# Evaluation_Board_v1_0.net
KiCad netlist of a schematic drawn in EAGLE
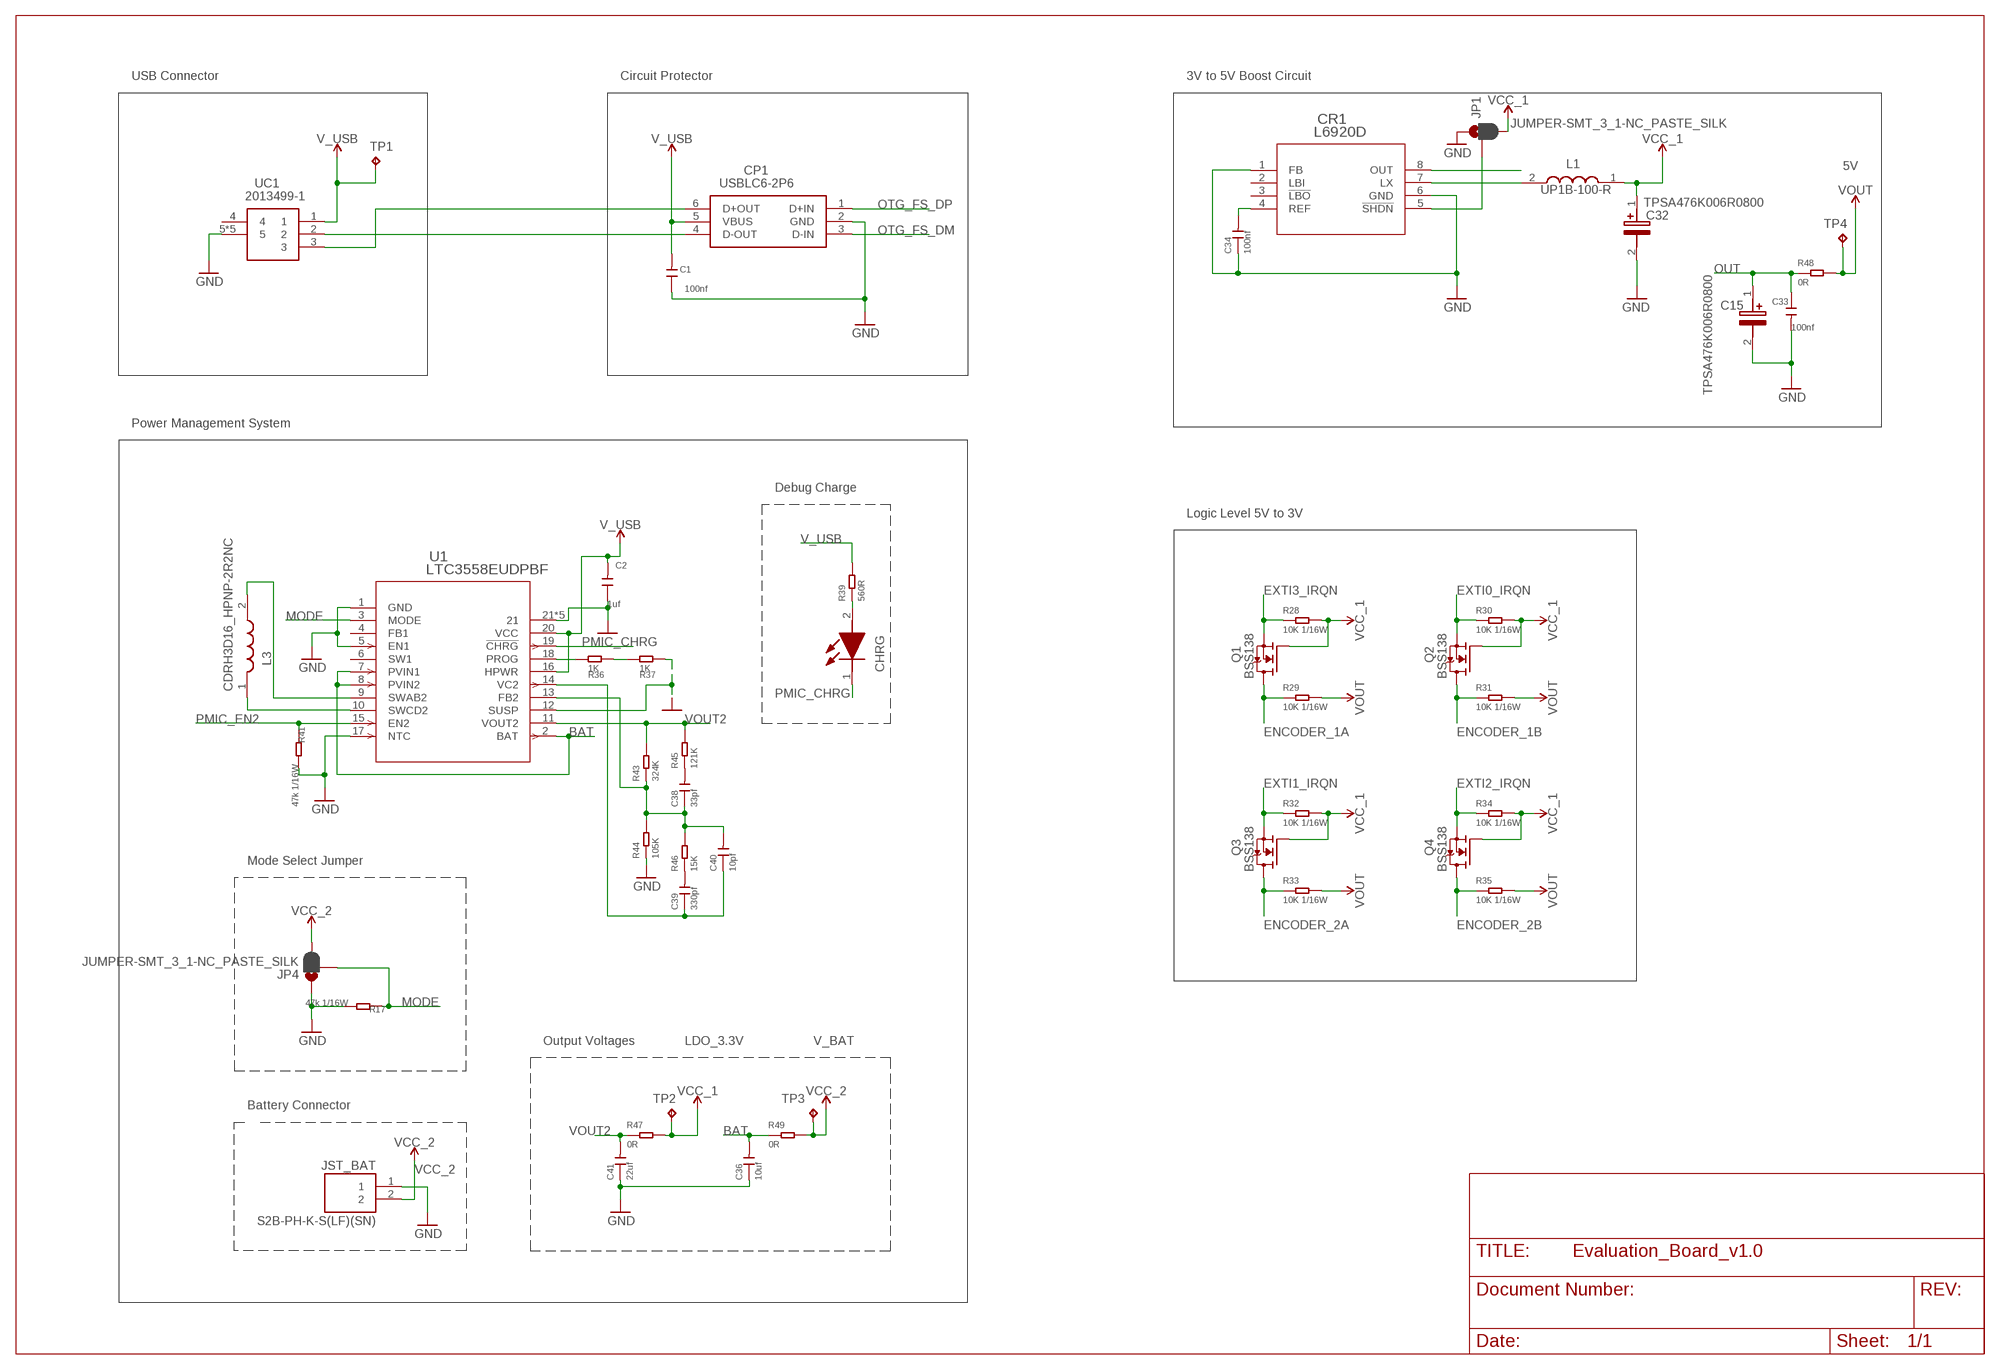
[diagram p0: schematic, sheet 1, part 1 of 3]
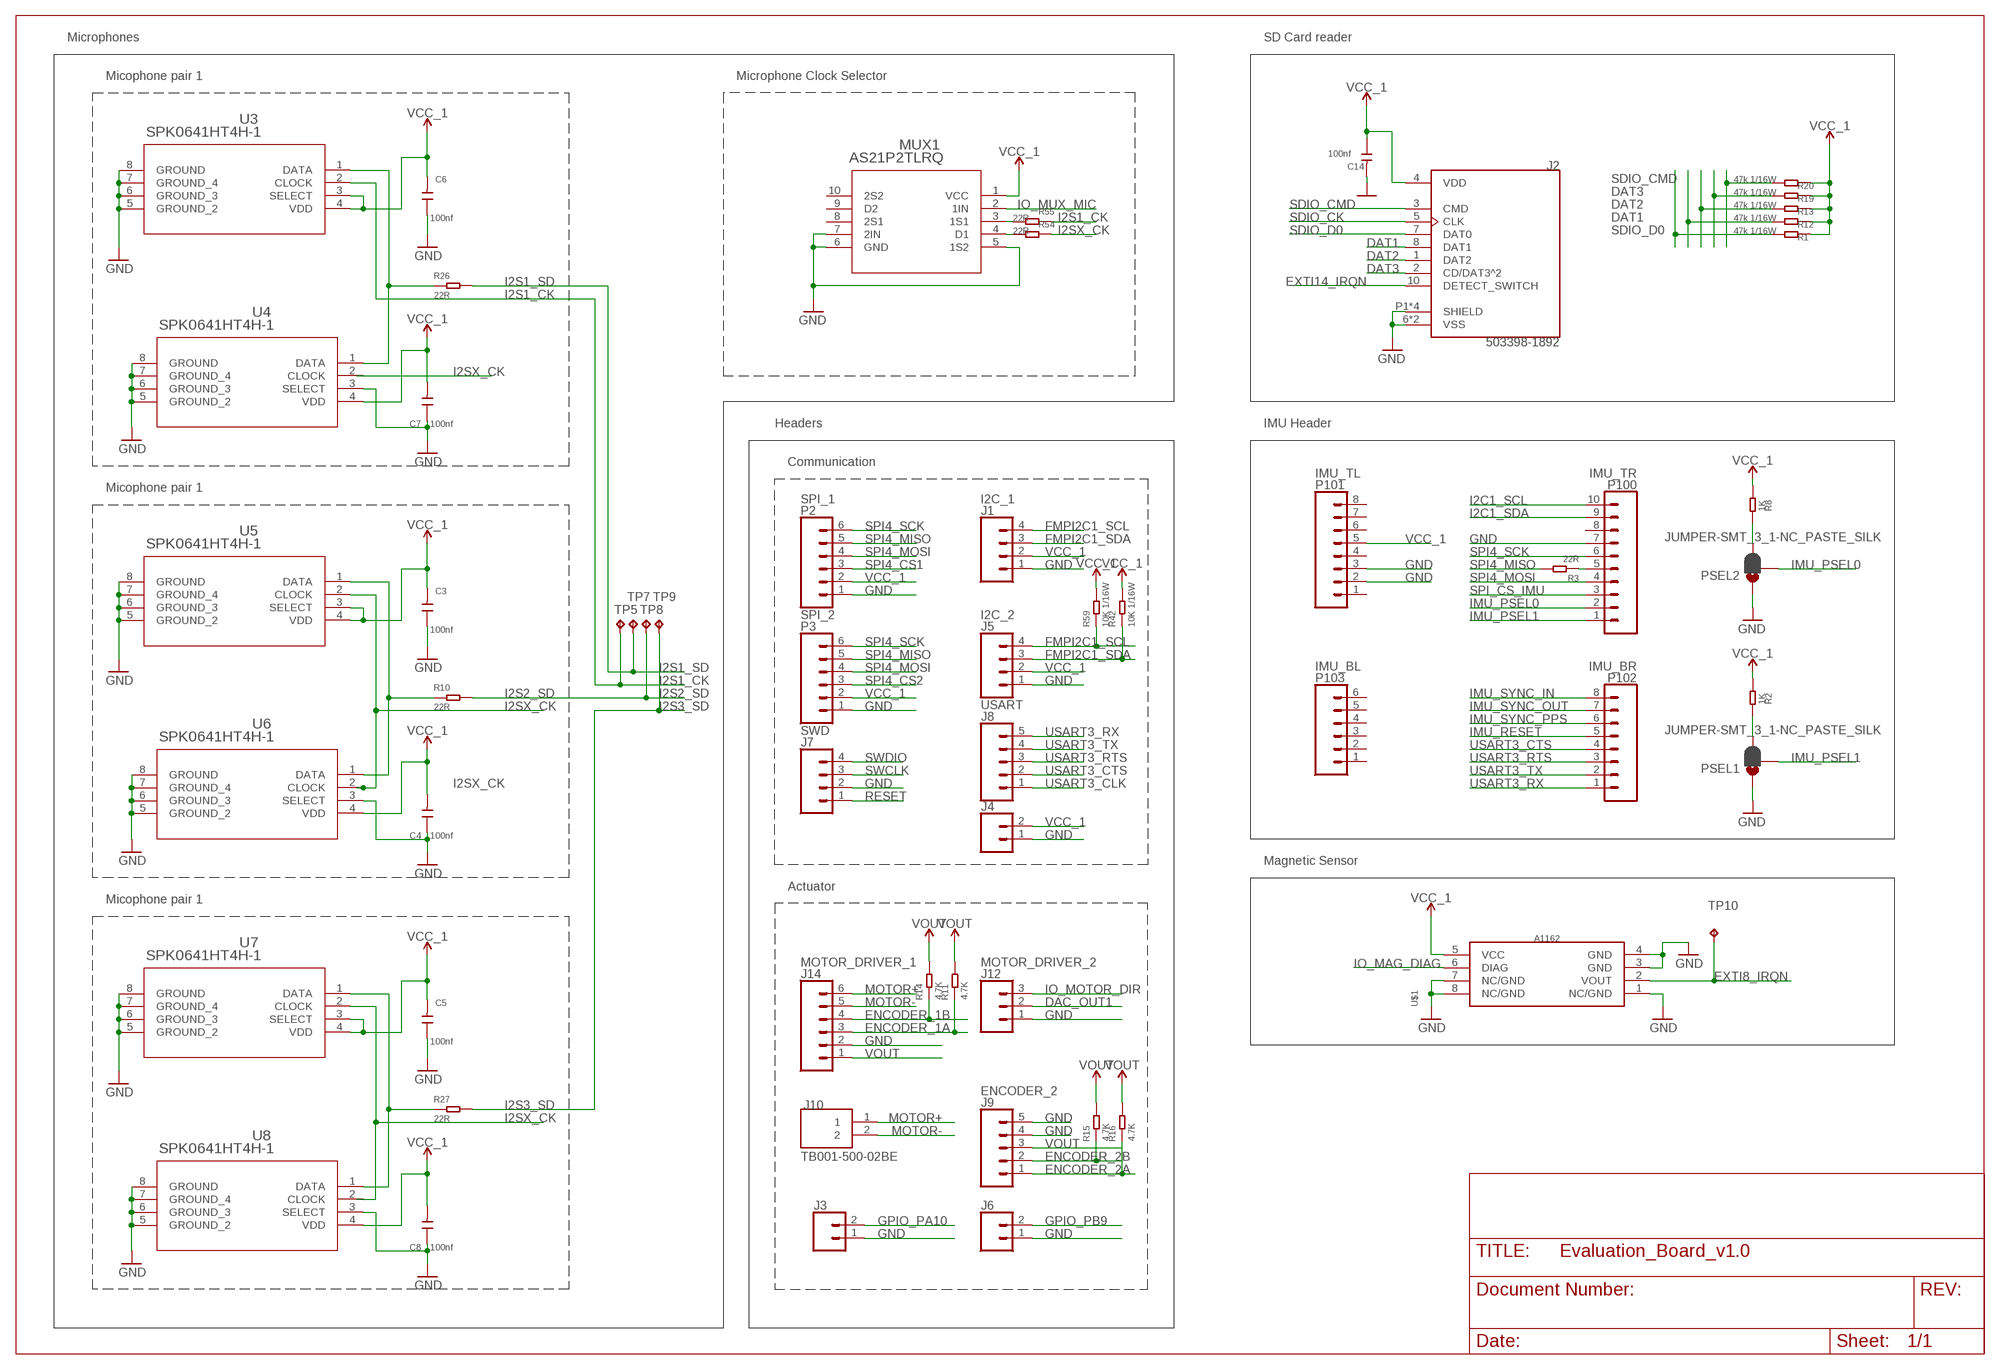
[diagram p1: schematic, sheet 1, part 2 of 3]
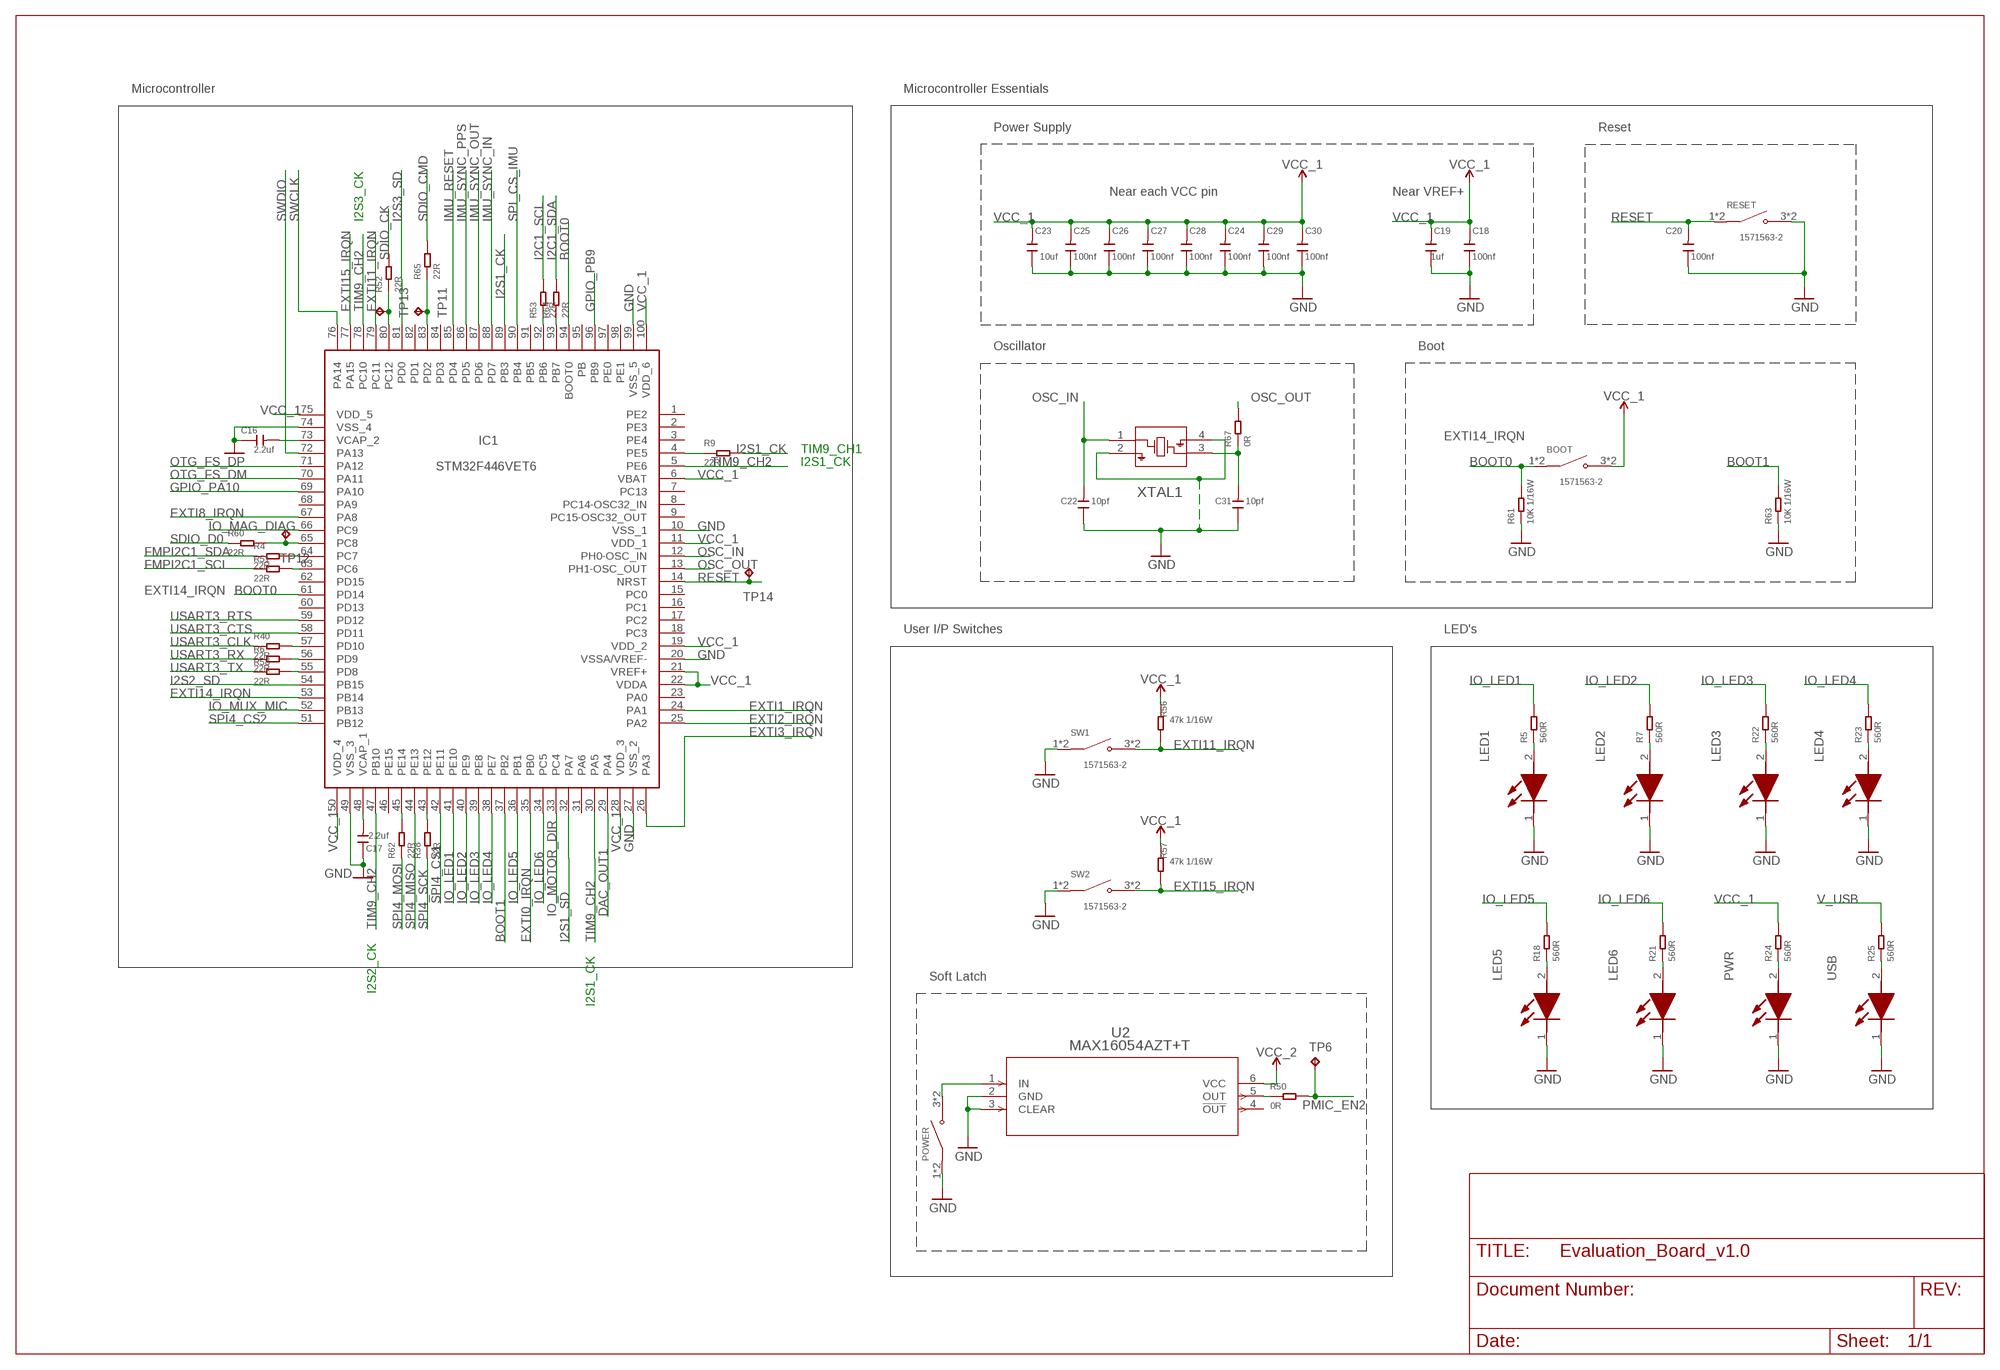
[diagram p2: schematic, sheet 1, part 3 of 3]

(export (version "E")
  (design (tool "Eeschema 10.0.6"))
  (components
    (comp (ref "BOOT")
      (value "1571563-2")
      (footprint "eagle-import:SW_1571563-2")
      (fields (field (name "DIGI-KEY_PART_NUMBER") "450-2057-1-ND") (field (name "MF") "TE Connectivity"))
      (libsource (lib "eagle-import") (part "1571563-2"))
    )
    (comp (ref "C1")
      (value "100nf")
      (footprint "eagle-import:C0402")
      (fields (field (name "MPN") "CC0402KRX7R8BB104"))
      (libsource (lib "eagle-import") (part "CERAMIC-100NF-25V-10%-X7R(0402)"))
    )
    (comp (ref "C2")
      (value "1uf")
      (footprint "eagle-import:C0402")
      (fields (field (name "MPN") "CC0402KRX5R6BB105"))
      (libsource (lib "eagle-import") (part "CERAMIC-1UF-10V-10%-X5R(0402)"))
    )
    (comp (ref "C3")
      (value "100nf")
      (footprint "eagle-import:C0402")
      (fields (field (name "MPN") "CC0402KRX7R8BB104"))
      (libsource (lib "eagle-import") (part "CERAMIC-100NF-25V-10%-X7R(0402)"))
    )
    (comp (ref "C4")
      (value "100nf")
      (footprint "eagle-import:C0402")
      (fields (field (name "MPN") "CC0402KRX7R8BB104"))
      (libsource (lib "eagle-import") (part "CERAMIC-100NF-25V-10%-X7R(0402)"))
    )
    (comp (ref "C5")
      (value "100nf")
      (footprint "eagle-import:C0402")
      (fields (field (name "MPN") "CC0402KRX7R8BB104"))
      (libsource (lib "eagle-import") (part "CERAMIC-100NF-25V-10%-X7R(0402)"))
    )
    (comp (ref "C6")
      (value "100nf")
      (footprint "eagle-import:C0402")
      (fields (field (name "MPN") "CC0402KRX7R8BB104"))
      (libsource (lib "eagle-import") (part "CERAMIC-100NF-25V-10%-X7R(0402)"))
    )
    (comp (ref "C7")
      (value "100nf")
      (footprint "eagle-import:C0402")
      (fields (field (name "MPN") "CC0402KRX7R8BB104"))
      (libsource (lib "eagle-import") (part "CERAMIC-100NF-25V-10%-X7R(0402)"))
    )
    (comp (ref "C8")
      (value "100nf")
      (footprint "eagle-import:C0402")
      (fields (field (name "MPN") "CC0402KRX7R8BB104"))
      (libsource (lib "eagle-import") (part "CERAMIC-100NF-25V-10%-X7R(0402)"))
    )
    (comp (ref "C14")
      (value "100nf")
      (footprint "eagle-import:C0402")
      (fields (field (name "MPN") "CC0402KRX7R8BB104"))
      (libsource (lib "eagle-import") (part "CERAMIC-100NF-25V-10%-X7R(0402)"))
    )
    (comp (ref "C15")
      (value "TPSA476K006R0800")
      (footprint "eagle-import:CAPPM3216X180N")
      (fields (field (name "MOUSER_PART_NUMBER") "581-TPSA476K006R0800"))
      (libsource (lib "eagle-import") (part "TPSA476K006R0800"))
    )
    (comp (ref "C16")
      (value "2.2uf")
      (footprint "eagle-import:C0603")
      (fields (field (name "MPN") "CC0603KRX7R6BB225"))
      (libsource (lib "eagle-import") (part "CERAMIC-2.2UF-10V-10%-X7R(0603)"))
    )
    (comp (ref "C17")
      (value "2.2uf")
      (footprint "eagle-import:C0603")
      (fields (field (name "MPN") "CC0603KRX7R6BB225"))
      (libsource (lib "eagle-import") (part "CERAMIC-2.2UF-10V-10%-X7R(0603)"))
    )
    (comp (ref "C18")
      (value "100nf")
      (footprint "eagle-import:C0402")
      (fields (field (name "MPN") "CC0402KRX7R8BB104"))
      (libsource (lib "eagle-import") (part "CERAMIC-100NF-25V-10%-X7R(0402)"))
    )
    (comp (ref "C19")
      (value "1uf")
      (footprint "eagle-import:C0402")
      (fields (field (name "MPN") "CC0402KRX5R6BB105"))
      (libsource (lib "eagle-import") (part "CERAMIC-1UF-10V-10%-X5R(0402)"))
    )
    (comp (ref "C20")
      (value "100nf")
      (footprint "eagle-import:C0402")
      (fields (field (name "MPN") "CC0402KRX7R8BB104"))
      (libsource (lib "eagle-import") (part "CERAMIC-100NF-25V-10%-X7R(0402)"))
    )
    (comp (ref "C22")
      (value "10pf")
      (footprint "eagle-import:C0402")
      (fields (field (name "MPN") "CC0402JRNPO9BN100"))
      (libsource (lib "eagle-import") (part "CERAMIC-10PF-50V-5%-NPO(0402)"))
    )
    (comp (ref "C23")
      (value "10uf")
      (footprint "eagle-import:C0603")
      (fields (field (name "MPN") "CC0603KRX5R6BB106"))
      (libsource (lib "eagle-import") (part "CERAMIC-10UF-10V-10%-X5R(0603)"))
    )
    (comp (ref "C24")
      (value "100nf")
      (footprint "eagle-import:C0402")
      (fields (field (name "MPN") "CC0402KRX7R8BB104"))
      (libsource (lib "eagle-import") (part "CERAMIC-100NF-25V-10%-X7R(0402)"))
    )
    (comp (ref "C25")
      (value "100nf")
      (footprint "eagle-import:C0402")
      (fields (field (name "MPN") "CC0402KRX7R8BB104"))
      (libsource (lib "eagle-import") (part "CERAMIC-100NF-25V-10%-X7R(0402)"))
    )
    (comp (ref "C26")
      (value "100nf")
      (footprint "eagle-import:C0402")
      (fields (field (name "MPN") "CC0402KRX7R8BB104"))
      (libsource (lib "eagle-import") (part "CERAMIC-100NF-25V-10%-X7R(0402)"))
    )
    (comp (ref "C27")
      (value "100nf")
      (footprint "eagle-import:C0402")
      (fields (field (name "MPN") "CC0402KRX7R8BB104"))
      (libsource (lib "eagle-import") (part "CERAMIC-100NF-25V-10%-X7R(0402)"))
    )
    (comp (ref "C28")
      (value "100nf")
      (footprint "eagle-import:C0402")
      (fields (field (name "MPN") "CC0402KRX7R8BB104"))
      (libsource (lib "eagle-import") (part "CERAMIC-100NF-25V-10%-X7R(0402)"))
    )
    (comp (ref "C29")
      (value "100nf")
      (footprint "eagle-import:C0402")
      (fields (field (name "MPN") "CC0402KRX7R8BB104"))
      (libsource (lib "eagle-import") (part "CERAMIC-100NF-25V-10%-X7R(0402)"))
    )
    (comp (ref "C30")
      (value "100nf")
      (footprint "eagle-import:C0402")
      (fields (field (name "MPN") "CC0402KRX7R8BB104"))
      (libsource (lib "eagle-import") (part "CERAMIC-100NF-25V-10%-X7R(0402)"))
    )
    (comp (ref "C31")
      (value "10pf")
      (footprint "eagle-import:C0402")
      (fields (field (name "MPN") "CC0402JRNPO9BN100"))
      (libsource (lib "eagle-import") (part "CERAMIC-10PF-50V-5%-NPO(0402)"))
    )
    (comp (ref "C32")
      (value "TPSA476K006R0800")
      (footprint "eagle-import:CAPPM3216X180N")
      (fields (field (name "MOUSER_PART_NUMBER") "581-TPSA476K006R0800"))
      (libsource (lib "eagle-import") (part "TPSA476K006R0800"))
    )
    (comp (ref "C33")
      (value "100nf")
      (footprint "eagle-import:C0402")
      (fields (field (name "MPN") "CC0402KRX7R8BB104"))
      (libsource (lib "eagle-import") (part "CERAMIC-100NF-25V-10%-X7R(0402)"))
    )
    (comp (ref "C34")
      (value "100nf")
      (footprint "eagle-import:C0402")
      (fields (field (name "MPN") "CC0402KRX7R8BB104"))
      (libsource (lib "eagle-import") (part "CERAMIC-100NF-25V-10%-X7R(0402)"))
    )
    (comp (ref "C36")
      (value "10uf")
      (footprint "eagle-import:C0603")
      (fields (field (name "MPN") "CC0603KRX5R6BB106"))
      (libsource (lib "eagle-import") (part "CERAMIC-10UF-10V-10%-X5R(0603)"))
    )
    (comp (ref "C38")
      (value "33pf")
      (footprint "eagle-import:C0402")
      (fields (field (name "MPN") "CC0402JRNPO9BN330"))
      (libsource (lib "eagle-import") (part "CERAMIC-33PF-50V-5%-NPO(0402)"))
    )
    (comp (ref "C39")
      (value "330pf")
      (footprint "eagle-import:C0402")
      (fields (field (name "MPN") "CC0402JRNPO9BN330"))
      (libsource (lib "eagle-import") (part "CERAMIC-33PF-50V-5%-NPO(0402)"))
    )
    (comp (ref "C40")
      (value "10pf")
      (footprint "eagle-import:C0402")
      (fields (field (name "MPN") "CC0402JRNPO9BN100"))
      (libsource (lib "eagle-import") (part "CERAMIC-10PF-50V-5%-NPO(0402)"))
    )
    (comp (ref "C41")
      (value "22uf")
      (footprint "eagle-import:C0805")
      (fields (field (name "MPN") "CC0805MKX5R5BB226"))
      (libsource (lib "eagle-import") (part "CERAMIC-22UF-6.3V-20%-X5R(0805)"))
    )
    (comp (ref "CHRG")
      (value "SML-P12MTT86R")
      (footprint "eagle-import:LEDM106X25N")
      (fields (field (name "MOUSER_PART_NUMBER") "755-SML-P12MTT86R"))
      (libsource (lib "eagle-import") (part "SML-P12MTT86R"))
    )
    (comp (ref "CP1")
      (value "USBLC6-2P6")
      (footprint "eagle-import:USBLC62P6")
      (fields (field (name "MOUSER_PART_NUMBER") "511-USBLC6-2P6"))
      (libsource (lib "eagle-import") (part "USBLC6-2P6"))
    )
    (comp (ref "CR1")
      (value "L6920D")
      (footprint "eagle-import:TSSOP8_STM")
      (libsource (lib "eagle-import") (part "L6920D"))
    )
    (comp (ref "IC1")
      (value "STM32F446VET6")
      (footprint "eagle-import:QFP50P1600X1600X160-100N")
      (fields (field (name "MOUSER_PART_NUMBER") "511-STM32F446VET6"))
      (libsource (lib "eagle-import") (part "STM32F446VET6"))
    )
    (comp (ref "J1")
      (value "I2C_1")
      (footprint "eagle-import:1X04")
      (libsource (lib "eagle-import") (part "CONN_04"))
    )
    (comp (ref "J2")
      (value "503398-1892")
      (footprint "eagle-import:MOLEX_503398-1892")
      (fields
        (field (name "DIGI-KEY_PART_NUMBER") "WM11190CT-ND")
        (field (name "MF") "Molex")
        (field (name "MP") "5033981892")
      )
      (libsource (lib "eagle-import") (part "503398-1892"))
    )
    (comp (ref "J3")
      (value "CONN_02")
      (footprint "eagle-import:1X02")
      (libsource (lib "eagle-import") (part "CONN_02"))
    )
    (comp (ref "J4")
      (value "CONN_02")
      (footprint "eagle-import:1X02")
      (libsource (lib "eagle-import") (part "CONN_02"))
    )
    (comp (ref "J5")
      (value "I2C_2")
      (footprint "eagle-import:1X04")
      (libsource (lib "eagle-import") (part "CONN_04"))
    )
    (comp (ref "J6")
      (value "CONN_02")
      (footprint "eagle-import:1X02")
      (libsource (lib "eagle-import") (part "CONN_02"))
    )
    (comp (ref "J7")
      (value "SWD")
      (footprint "eagle-import:1X04")
      (libsource (lib "eagle-import") (part "CONN_04"))
    )
    (comp (ref "J8")
      (value "USART")
      (footprint "eagle-import:1X05")
      (libsource (lib "eagle-import") (part "CONN_05"))
    )
    (comp (ref "J9")
      (value "ENCODER_2")
      (footprint "eagle-import:1X05")
      (libsource (lib "eagle-import") (part "CONN_05"))
    )
    (comp (ref "J10")
      (value "TB001-500-02BE")
      (footprint "eagle-import:CUI_TB001-500-02BE")
      (fields (field (name "DIGI-KEY_PART_NUMBER") "102-6134-ND") (field (name "MF") "CUI Devices"))
      (libsource (lib "eagle-import") (part "TB001-500-02BE"))
    )
    (comp (ref "J12")
      (value "MOTOR_DRIVER_2")
      (footprint "eagle-import:1X03")
      (libsource (lib "eagle-import") (part "CONN_03"))
    )
    (comp (ref "J14")
      (value "MOTOR_DRIVER_1")
      (footprint "eagle-import:MOLEX-1X6")
      (libsource (lib "eagle-import") (part "CONN_06POLAR"))
    )
    (comp (ref "JP1")
      (value "JUMPER-SMT_3_1-NC_PASTE_SILK")
      (footprint "eagle-import:SMT-JUMPER_3_1-NC_PASTE_SILK")
      (libsource (lib "eagle-import") (part "JUMPER-SMT_3_1-NC_PASTE_SILK"))
    )
    (comp (ref "JP4")
      (value "JUMPER-SMT_3_1-NC_PASTE_SILK")
      (footprint "eagle-import:SMT-JUMPER_3_1-NC_PASTE_SILK")
      (libsource (lib "eagle-import") (part "JUMPER-SMT_3_1-NC_PASTE_SILK"))
    )
    (comp (ref "JST_BAT")
      (value "S2B-PH-K-S(LF)(SN)")
      (footprint "eagle-import:JST_S2B-PH-K-S(LF)(SN)")
      (fields
        (field (name "DIGI-KEY_PART_NUMBER") "455-1719-ND")
        (field (name "MF") "JST Sales America Inc.")
      )
      (libsource (lib "eagle-import") (part "S2B-PH-K-S(LF)(SN)"))
    )
    (comp (ref "L1")
      (value "UP1B-100-R")
      (footprint "eagle-import:INDM9060X500N")
      (libsource (lib "eagle-import") (part "UP1B-100-R"))
    )
    (comp (ref "L3")
      (value "CDRH3D16_HPNP-2R2NC")
      (footprint "eagle-import:CDRH3D16HPNP2R2NC")
      (fields
        (field (name "MANUFACTURER_PART_NUMBER") "CDRH3D16/HPNP-2R2NC")
        (field (name "MOUSER_PART_NUMBER") "851-CDRH3D16HPNP2R2")
      )
      (libsource (lib "eagle-import") (part "CDRH3D16_HPNP-2R2NC"))
    )
    (comp (ref "LED1")
      (value "SML-P12MTT86R")
      (footprint "eagle-import:LEDM106X25N")
      (fields (field (name "MOUSER_PART_NUMBER") "755-SML-P12MTT86R"))
      (libsource (lib "eagle-import") (part "SML-P12MTT86R"))
    )
    (comp (ref "LED2")
      (value "SML-P12MTT86R")
      (footprint "eagle-import:LEDM106X25N")
      (fields (field (name "MOUSER_PART_NUMBER") "755-SML-P12MTT86R"))
      (libsource (lib "eagle-import") (part "SML-P12MTT86R"))
    )
    (comp (ref "LED3")
      (value "SML-P12MTT86R")
      (footprint "eagle-import:LEDM106X25N")
      (fields (field (name "MOUSER_PART_NUMBER") "755-SML-P12MTT86R"))
      (libsource (lib "eagle-import") (part "SML-P12MTT86R"))
    )
    (comp (ref "LED4")
      (value "SML-P12MTT86R")
      (footprint "eagle-import:LEDM106X25N")
      (fields (field (name "MOUSER_PART_NUMBER") "755-SML-P12MTT86R"))
      (libsource (lib "eagle-import") (part "SML-P12MTT86R"))
    )
    (comp (ref "LED5")
      (value "SML-P12MTT86R")
      (footprint "eagle-import:LEDM106X25N")
      (fields (field (name "MOUSER_PART_NUMBER") "755-SML-P12MTT86R"))
      (libsource (lib "eagle-import") (part "SML-P12MTT86R"))
    )
    (comp (ref "LED6")
      (value "SML-P12MTT86R")
      (footprint "eagle-import:LEDM106X25N")
      (fields (field (name "MOUSER_PART_NUMBER") "755-SML-P12MTT86R"))
      (libsource (lib "eagle-import") (part "SML-P12MTT86R"))
    )
    (comp (ref "MUX1")
      (value "AS21P2TLRQ")
      (footprint "eagle-import:QFN10_1P8X1P4X0P5_STM")
      (fields (field (name "COPYRIGHT") "Copyright (C) 2018 Accelerated Designs. All rights reserved"))
      (libsource (lib "eagle-import") (part "AS21P2TLRQ"))
    )
    (comp (ref "P2")
      (value "SPI_1")
      (footprint "eagle-import:1X06")
      (libsource (lib "eagle-import") (part "CONN_06SILK_FEMALE_PTH"))
    )
    (comp (ref "P3")
      (value "SPI_2")
      (footprint "eagle-import:1X06")
      (libsource (lib "eagle-import") (part "CONN_06SILK_FEMALE_PTH"))
    )
    (comp (ref "P100")
      (value "IMU_TR")
      (footprint "eagle-import:1X10")
      (libsource (lib "eagle-import") (part "CONN_10{dblquote}"))
    )
    (comp (ref "P101")
      (value "IMU_TL")
      (footprint "eagle-import:1X08")
      (libsource (lib "eagle-import") (part "CONN_08{dblquote}"))
    )
    (comp (ref "P102")
      (value "IMU_BR")
      (footprint "eagle-import:1X08")
      (libsource (lib "eagle-import") (part "CONN_08{dblquote}"))
    )
    (comp (ref "P103")
      (value "IMU_BL")
      (footprint "eagle-import:1X06")
      (libsource (lib "eagle-import") (part "CONN_06SILK_FEMALE_PTH"))
    )
    (comp (ref "POWER")
      (value "1571563-2")
      (footprint "eagle-import:SW_1571563-2")
      (fields (field (name "DIGI-KEY_PART_NUMBER") "450-2057-1-ND") (field (name "MF") "TE Connectivity"))
      (libsource (lib "eagle-import") (part "1571563-2"))
    )
    (comp (ref "PSEL1")
      (value "JUMPER-SMT_3_1-NC_PASTE_SILK")
      (footprint "eagle-import:SMT-JUMPER_3_1-NC_PASTE_SILK")
      (libsource (lib "eagle-import") (part "JUMPER-SMT_3_1-NC_PASTE_SILK"))
    )
    (comp (ref "PSEL2")
      (value "JUMPER-SMT_3_1-NC_PASTE_SILK")
      (footprint "eagle-import:SMT-JUMPER_3_1-NC_PASTE_SILK")
      (libsource (lib "eagle-import") (part "JUMPER-SMT_3_1-NC_PASTE_SILK"))
    )
    (comp (ref "PWR")
      (value "SML-P12MTT86R")
      (footprint "eagle-import:LEDM106X25N")
      (fields (field (name "MOUSER_PART_NUMBER") "755-SML-P12MTT86R"))
      (libsource (lib "eagle-import") (part "SML-P12MTT86R"))
    )
    (comp (ref "Q1")
      (value "BSS138")
      (footprint "eagle-import:SOT95P240X111-3N")
      (fields (field (name "DIGI-KEY_PART_NUMBER") "BSS138WCT-ND") (field (name "MF") "ON Semiconductor"))
      (libsource (lib "eagle-import") (part "BSS138"))
    )
    (comp (ref "Q2")
      (value "BSS138")
      (footprint "eagle-import:SOT95P240X111-3N")
      (fields (field (name "DIGI-KEY_PART_NUMBER") "BSS138WCT-ND") (field (name "MF") "ON Semiconductor"))
      (libsource (lib "eagle-import") (part "BSS138"))
    )
    (comp (ref "Q3")
      (value "BSS138")
      (footprint "eagle-import:SOT95P240X111-3N")
      (fields (field (name "DIGI-KEY_PART_NUMBER") "BSS138WCT-ND") (field (name "MF") "ON Semiconductor"))
      (libsource (lib "eagle-import") (part "BSS138"))
    )
    (comp (ref "Q4")
      (value "BSS138")
      (footprint "eagle-import:SOT95P240X111-3N")
      (fields (field (name "DIGI-KEY_PART_NUMBER") "BSS138WCT-ND") (field (name "MF") "ON Semiconductor"))
      (libsource (lib "eagle-import") (part "BSS138"))
    )
    (comp (ref "R1")
      (value "47k 1/16W")
      (footprint "eagle-import:R0402")
      (fields (field (name "MPN") "RC0402JR-070RL"))
      (libsource (lib "eagle-import") (part "SMD-RES-47R-1%-1/16W(0402)"))
    )
    (comp (ref "R2")
      (value "1K")
      (footprint "eagle-import:R0603")
      (fields (field (name "MPN") "RC0603FR-071KL"))
      (libsource (lib "eagle-import") (part "SMD-RES-1K-1%-1/10W(0603)"))
    )
    (comp (ref "R3")
      (value "22R")
      (footprint "eagle-import:R0402")
      (fields (field (name "MPN") "RC0402FR-0722RL"))
      (libsource (lib "eagle-import") (part "SMD-RES-22R-1%-1/16W(0402)"))
    )
    (comp (ref "R4")
      (value "22R")
      (footprint "eagle-import:R0402")
      (fields (field (name "MPN") "RC0402FR-0722RL"))
      (libsource (lib "eagle-import") (part "SMD-RES-22R-1%-1/16W(0402)"))
    )
    (comp (ref "R5")
      (value "560R")
      (footprint "eagle-import:R0603")
      (fields (field (name "MPN") "RC0603FR-071K5L"))
      (libsource (lib "eagle-import") (part "SMD-RES-560R-5%-1/10W(0603)"))
    )
    (comp (ref "R6")
      (value "22R")
      (footprint "eagle-import:R0402")
      (fields (field (name "MPN") "RC0402FR-0722RL"))
      (libsource (lib "eagle-import") (part "SMD-RES-22R-1%-1/16W(0402)"))
    )
    (comp (ref "R7")
      (value "560R")
      (footprint "eagle-import:R0603")
      (fields (field (name "MPN") "RC0603FR-071K5L"))
      (libsource (lib "eagle-import") (part "SMD-RES-560R-5%-1/10W(0603)"))
    )
    (comp (ref "R8")
      (value "1K")
      (footprint "eagle-import:R0603")
      (fields (field (name "MPN") "RC0603FR-071KL"))
      (libsource (lib "eagle-import") (part "SMD-RES-1K-1%-1/10W(0603)"))
    )
    (comp (ref "R9")
      (value "22R")
      (footprint "eagle-import:R0402")
      (fields (field (name "MPN") "RC0402FR-0722RL"))
      (libsource (lib "eagle-import") (part "SMD-RES-22R-1%-1/16W(0402)"))
    )
    (comp (ref "R10")
      (value "22R")
      (footprint "eagle-import:R0402")
      (fields (field (name "MPN") "RC0402FR-0722RL"))
      (libsource (lib "eagle-import") (part "SMD-RES-22R-1%-1/16W(0402)"))
    )
    (comp (ref "R11")
      (value "4.7K")
      (footprint "eagle-import:R0402")
      (fields (field (name "MPN") "RC0402JR-070RL"))
      (libsource (lib "eagle-import") (part "SMD-RES-3.3K-1%-1/16W(0402)"))
    )
    (comp (ref "R12")
      (value "47k 1/16W")
      (footprint "eagle-import:R0402")
      (fields (field (name "MPN") "RC0402JR-070RL"))
      (libsource (lib "eagle-import") (part "SMD-RES-47R-1%-1/16W(0402)"))
    )
    (comp (ref "R13")
      (value "47k 1/16W")
      (footprint "eagle-import:R0402")
      (fields (field (name "MPN") "RC0402JR-070RL"))
      (libsource (lib "eagle-import") (part "SMD-RES-47R-1%-1/16W(0402)"))
    )
    (comp (ref "R14")
      (value "4.7K")
      (footprint "eagle-import:R0402")
      (fields (field (name "MPN") "RC0402JR-070RL"))
      (libsource (lib "eagle-import") (part "SMD-RES-3.3K-1%-1/16W(0402)"))
    )
    (comp (ref "R15")
      (value "4.7K")
      (footprint "eagle-import:R0402")
      (fields (field (name "MPN") "RC0402JR-070RL"))
      (libsource (lib "eagle-import") (part "SMD-RES-3.3K-1%-1/16W(0402)"))
    )
    (comp (ref "R16")
      (value "4.7K")
      (footprint "eagle-import:R0402")
      (fields (field (name "MPN") "RC0402JR-070RL"))
      (libsource (lib "eagle-import") (part "SMD-RES-3.3K-1%-1/16W(0402)"))
    )
    (comp (ref "R17")
      (value "47k 1/16W")
      (footprint "eagle-import:R0402")
      (fields (field (name "MPN") "RC0402JR-070RL"))
      (libsource (lib "eagle-import") (part "SMD-RES-47R-1%-1/16W(0402)"))
    )
    (comp (ref "R18")
      (value "560R")
      (footprint "eagle-import:R0603")
      (fields (field (name "MPN") "RC0603FR-071K5L"))
      (libsource (lib "eagle-import") (part "SMD-RES-560R-5%-1/10W(0603)"))
    )
    (comp (ref "R19")
      (value "47k 1/16W")
      (footprint "eagle-import:R0402")
      (fields (field (name "MPN") "RC0402JR-070RL"))
      (libsource (lib "eagle-import") (part "SMD-RES-47R-1%-1/16W(0402)"))
    )
    (comp (ref "R20")
      (value "47k 1/16W")
      (footprint "eagle-import:R0402")
      (fields (field (name "MPN") "RC0402JR-070RL"))
      (libsource (lib "eagle-import") (part "SMD-RES-47R-1%-1/16W(0402)"))
    )
    (comp (ref "R21")
      (value "560R")
      (footprint "eagle-import:R0603")
      (fields (field (name "MPN") "RC0603FR-071K5L"))
      (libsource (lib "eagle-import") (part "SMD-RES-560R-5%-1/10W(0603)"))
    )
    (comp (ref "R22")
      (value "560R")
      (footprint "eagle-import:R0603")
      (fields (field (name "MPN") "RC0603FR-071K5L"))
      (libsource (lib "eagle-import") (part "SMD-RES-560R-5%-1/10W(0603)"))
    )
    (comp (ref "R23")
      (value "560R")
      (footprint "eagle-import:R0603")
      (fields (field (name "MPN") "RC0603FR-071K5L"))
      (libsource (lib "eagle-import") (part "SMD-RES-560R-5%-1/10W(0603)"))
    )
    (comp (ref "R24")
      (value "560R")
      (footprint "eagle-import:R0603")
      (fields (field (name "MPN") "RC0603FR-071K5L"))
      (libsource (lib "eagle-import") (part "SMD-RES-560R-5%-1/10W(0603)"))
    )
    (comp (ref "R25")
      (value "560R")
      (footprint "eagle-import:R0603")
      (fields (field (name "MPN") "RC0603FR-071K5L"))
      (libsource (lib "eagle-import") (part "SMD-RES-560R-5%-1/10W(0603)"))
    )
    (comp (ref "R26")
      (value "22R")
      (footprint "eagle-import:R0402")
      (fields (field (name "MPN") "RC0402FR-0722RL"))
      (libsource (lib "eagle-import") (part "SMD-RES-22R-1%-1/16W(0402)"))
    )
    (comp (ref "R27")
      (value "22R")
      (footprint "eagle-import:R0402")
      (fields (field (name "MPN") "RC0402FR-0722RL"))
      (libsource (lib "eagle-import") (part "SMD-RES-22R-1%-1/16W(0402)"))
    )
    (comp (ref "R28")
      (value "10K 1/16W")
      (footprint "eagle-import:R0402")
      (fields (field (name "MPN") "RC0402FR-0710KL"))
      (libsource (lib "eagle-import") (part "SMD-RES-10K-1%-1/16W(0402)"))
    )
    (comp (ref "R29")
      (value "10K 1/16W")
      (footprint "eagle-import:R0402")
      (fields (field (name "MPN") "RC0402FR-0710KL"))
      (libsource (lib "eagle-import") (part "SMD-RES-10K-1%-1/16W(0402)"))
    )
    (comp (ref "R30")
      (value "10K 1/16W")
      (footprint "eagle-import:R0402")
      (fields (field (name "MPN") "RC0402FR-0710KL"))
      (libsource (lib "eagle-import") (part "SMD-RES-10K-1%-1/16W(0402)"))
    )
    (comp (ref "R31")
      (value "10K 1/16W")
      (footprint "eagle-import:R0402")
      (fields (field (name "MPN") "RC0402FR-0710KL"))
      (libsource (lib "eagle-import") (part "SMD-RES-10K-1%-1/16W(0402)"))
    )
    (comp (ref "R32")
      (value "10K 1/16W")
      (footprint "eagle-import:R0402")
      (fields (field (name "MPN") "RC0402FR-0710KL"))
      (libsource (lib "eagle-import") (part "SMD-RES-10K-1%-1/16W(0402)"))
    )
    (comp (ref "R33")
      (value "10K 1/16W")
      (footprint "eagle-import:R0402")
      (fields (field (name "MPN") "RC0402FR-0710KL"))
      (libsource (lib "eagle-import") (part "SMD-RES-10K-1%-1/16W(0402)"))
    )
    (comp (ref "R34")
      (value "10K 1/16W")
      (footprint "eagle-import:R0402")
      (fields (field (name "MPN") "RC0402FR-0710KL"))
      (libsource (lib "eagle-import") (part "SMD-RES-10K-1%-1/16W(0402)"))
    )
    (comp (ref "R35")
      (value "10K 1/16W")
      (footprint "eagle-import:R0402")
      (fields (field (name "MPN") "RC0402FR-0710KL"))
      (libsource (lib "eagle-import") (part "SMD-RES-10K-1%-1/16W(0402)"))
    )
    (comp (ref "R36")
      (value "1K")
      (footprint "eagle-import:R0603")
      (fields (field (name "MPN") "RC0603FR-071KL"))
      (libsource (lib "eagle-import") (part "SMD-RES-1K-1%-1/10W(0603)"))
    )
    (comp (ref "R37")
      (value "1K")
      (footprint "eagle-import:R0603")
      (fields (field (name "MPN") "RC0603FR-071KL"))
      (libsource (lib "eagle-import") (part "SMD-RES-1K-1%-1/10W(0603)"))
    )
    (comp (ref "R38")
      (value "22R")
      (footprint "eagle-import:R0402")
      (fields (field (name "MPN") "RC0402FR-0722RL"))
      (libsource (lib "eagle-import") (part "SMD-RES-22R-1%-1/16W(0402)"))
    )
    (comp (ref "R39")
      (value "560R")
      (footprint "eagle-import:R0603")
      (fields (field (name "MPN") "RC0603FR-071K5L"))
      (libsource (lib "eagle-import") (part "SMD-RES-560R-5%-1/10W(0603)"))
    )
    (comp (ref "R40")
      (value "22R")
      (footprint "eagle-import:R0402")
      (fields (field (name "MPN") "RC0402FR-0722RL"))
      (libsource (lib "eagle-import") (part "SMD-RES-22R-1%-1/16W(0402)"))
    )
    (comp (ref "R41")
      (value "47k 1/16W")
      (footprint "eagle-import:R0402")
      (fields (field (name "MPN") "RC0402JR-070RL"))
      (libsource (lib "eagle-import") (part "SMD-RES-47R-1%-1/16W(0402)"))
    )
    (comp (ref "R42")
      (value "10K 1/16W")
      (footprint "eagle-import:R0402")
      (fields (field (name "MPN") "RC0402FR-0710KL"))
      (libsource (lib "eagle-import") (part "SMD-RES-10K-1%-1/16W(0402)"))
    )
    (comp (ref "R43")
      (value "324K")
      (footprint "eagle-import:R0603")
      (fields (field (name "MPN") "RC0603FR-071K5L"))
      (libsource (lib "eagle-import") (part "SMD-RES-470K-1%-1/10W(0603)"))
    )
    (comp (ref "R44")
      (value "105K")
      (footprint "eagle-import:R0603")
      (fields (field (name "MPN") "RC0603FR-071K5L"))
      (libsource (lib "eagle-import") (part "SMD-RES-470K-1%-1/10W(0603)"))
    )
    (comp (ref "R45")
      (value "121K")
      (footprint "eagle-import:R0603")
      (fields (field (name "MPN") "RC0603FR-071K5L"))
      (libsource (lib "eagle-import") (part "SMD-RES-470K-1%-1/10W(0603)"))
    )
    (comp (ref "R46")
      (value "15K")
      (footprint "eagle-import:R0603")
      (fields (field (name "MPN") "RC0603FR-071K5L"))
      (libsource (lib "eagle-import") (part "SMD-RES-470K-1%-1/10W(0603)"))
    )
    (comp (ref "R47")
      (value "0R")
      (footprint "eagle-import:R0805")
      (fields (field (name "MPN") "RC0805JR-071KL"))
      (libsource (lib "eagle-import") (part "SMD-RES-0R-1%-1/8W(0805)"))
    )
    (comp (ref "R48")
      (value "0R")
      (footprint "eagle-import:R0805")
      (fields (field (name "MPN") "RC0805JR-071KL"))
      (libsource (lib "eagle-import") (part "SMD-RES-0R-1%-1/8W(0805)"))
    )
    (comp (ref "R49")
      (value "0R")
      (footprint "eagle-import:R0805")
      (fields (field (name "MPN") "RC0805JR-071KL"))
      (libsource (lib "eagle-import") (part "SMD-RES-0R-1%-1/8W(0805)"))
    )
    (comp (ref "R50")
      (value "0R")
      (footprint "eagle-import:R0805")
      (fields (field (name "MPN") "RC0805JR-071KL"))
      (libsource (lib "eagle-import") (part "SMD-RES-0R-1%-1/8W(0805)"))
    )
    (comp (ref "R51")
      (value "22R")
      (footprint "eagle-import:R0402")
      (fields (field (name "MPN") "RC0402FR-0722RL"))
      (libsource (lib "eagle-import") (part "SMD-RES-22R-1%-1/16W(0402)"))
    )
    (comp (ref "R52")
      (value "22R")
      (footprint "eagle-import:R0402")
      (fields (field (name "MPN") "RC0402FR-0722RL"))
      (libsource (lib "eagle-import") (part "SMD-RES-22R-1%-1/16W(0402)"))
    )
    (comp (ref "R53")
      (value "22R")
      (footprint "eagle-import:R0402")
      (fields (field (name "MPN") "RC0402FR-0722RL"))
      (libsource (lib "eagle-import") (part "SMD-RES-22R-1%-1/16W(0402)"))
    )
    (comp (ref "R54")
      (value "22R")
      (footprint "eagle-import:R0402")
      (fields (field (name "MPN") "RC0402FR-0722RL"))
      (libsource (lib "eagle-import") (part "SMD-RES-22R-1%-1/16W(0402)"))
    )
    (comp (ref "R55")
      (value "22R")
      (footprint "eagle-import:R0402")
      (fields (field (name "MPN") "RC0402FR-0722RL"))
      (libsource (lib "eagle-import") (part "SMD-RES-22R-1%-1/16W(0402)"))
    )
    (comp (ref "R56")
      (value "47k 1/16W")
      (footprint "eagle-import:R0402")
      (fields (field (name "MPN") "RC0402JR-070RL"))
      (libsource (lib "eagle-import") (part "SMD-RES-47R-1%-1/16W(0402)"))
    )
    (comp (ref "R57")
      (value "47k 1/16W")
      (footprint "eagle-import:R0402")
      (fields (field (name "MPN") "RC0402JR-070RL"))
      (libsource (lib "eagle-import") (part "SMD-RES-47R-1%-1/16W(0402)"))
    )
    (comp (ref "R58")
      (value "22R")
      (footprint "eagle-import:R0402")
      (fields (field (name "MPN") "RC0402FR-0722RL"))
      (libsource (lib "eagle-import") (part "SMD-RES-22R-1%-1/16W(0402)"))
    )
    (comp (ref "R59")
      (value "10K 1/16W")
      (footprint "eagle-import:R0402")
      (fields (field (name "MPN") "RC0402FR-0710KL"))
      (libsource (lib "eagle-import") (part "SMD-RES-10K-1%-1/16W(0402)"))
    )
    (comp (ref "R60")
      (value "22R")
      (footprint "eagle-import:R0402")
      (fields (field (name "MPN") "RC0402FR-0722RL"))
      (libsource (lib "eagle-import") (part "SMD-RES-22R-1%-1/16W(0402)"))
    )
    (comp (ref "R61")
      (value "10K 1/16W")
      (footprint "eagle-import:R0402")
      (fields (field (name "MPN") "RC0402FR-0710KL"))
      (libsource (lib "eagle-import") (part "SMD-RES-10K-1%-1/16W(0402)"))
    )
    (comp (ref "R62")
      (value "22R")
      (footprint "eagle-import:R0402")
      (fields (field (name "MPN") "RC0402FR-0722RL"))
      (libsource (lib "eagle-import") (part "SMD-RES-22R-1%-1/16W(0402)"))
    )
    (comp (ref "R63")
      (value "10K 1/16W")
      (footprint "eagle-import:R0402")
      (fields (field (name "MPN") "RC0402FR-0710KL"))
      (libsource (lib "eagle-import") (part "SMD-RES-10K-1%-1/16W(0402)"))
    )
    (comp (ref "R64")
      (value "22R")
      (footprint "eagle-import:R0402")
      (fields (field (name "MPN") "RC0402FR-0722RL"))
      (libsource (lib "eagle-import") (part "SMD-RES-22R-1%-1/16W(0402)"))
    )
    (comp (ref "R65")
      (value "22R")
      (footprint "eagle-import:R0402")
      (fields (field (name "MPN") "RC0402FR-0722RL"))
      (libsource (lib "eagle-import") (part "SMD-RES-22R-1%-1/16W(0402)"))
    )
    (comp (ref "R67")
      (value "0R")
      (footprint "eagle-import:R0402")
      (fields (field (name "MPN") "RC0402JR-070RL"))
      (libsource (lib "eagle-import") (part "SMD-RES-0R-5%-1/16W(0402)"))
    )
    (comp (ref "RESET")
      (value "1571563-2")
      (footprint "eagle-import:SW_1571563-2")
      (fields (field (name "DIGI-KEY_PART_NUMBER") "450-2057-1-ND") (field (name "MF") "TE Connectivity"))
      (libsource (lib "eagle-import") (part "1571563-2"))
    )
    (comp (ref "SW1")
      (value "1571563-2")
      (footprint "eagle-import:SW_1571563-2")
      (fields (field (name "DIGI-KEY_PART_NUMBER") "450-2057-1-ND") (field (name "MF") "TE Connectivity"))
      (libsource (lib "eagle-import") (part "1571563-2"))
    )
    (comp (ref "SW2")
      (value "1571563-2")
      (footprint "eagle-import:SW_1571563-2")
      (fields (field (name "DIGI-KEY_PART_NUMBER") "450-2057-1-ND") (field (name "MF") "TE Connectivity"))
      (libsource (lib "eagle-import") (part "1571563-2"))
    )
    (comp (ref "TP1")
      (value "TPB1,27")
      (footprint "eagle-import:B1,27")
      (libsource (lib "eagle-import") (part "TPB1,27"))
    )
    (comp (ref "TP2")
      (value "TPB1,27")
      (footprint "eagle-import:B1,27")
      (libsource (lib "eagle-import") (part "TPB1,27"))
    )
    (comp (ref "TP3")
      (value "TPB1,27")
      (footprint "eagle-import:B1,27")
      (libsource (lib "eagle-import") (part "TPB1,27"))
    )
    (comp (ref "TP4")
      (value "TPB1,27")
      (footprint "eagle-import:B1,27")
      (libsource (lib "eagle-import") (part "TPB1,27"))
    )
    (comp (ref "TP5")
      (value "TPB1,27")
      (footprint "eagle-import:B1,27")
      (libsource (lib "eagle-import") (part "TPB1,27"))
    )
    (comp (ref "TP6")
      (value "TPB1,27")
      (footprint "eagle-import:B1,27")
      (libsource (lib "eagle-import") (part "TPB1,27"))
    )
    (comp (ref "TP7")
      (value "TPB1,27")
      (footprint "eagle-import:B1,27")
      (libsource (lib "eagle-import") (part "TPB1,27"))
    )
    (comp (ref "TP8")
      (value "TPB1,27")
      (footprint "eagle-import:B1,27")
      (libsource (lib "eagle-import") (part "TPB1,27"))
    )
    (comp (ref "TP9")
      (value "TPB1,27")
      (footprint "eagle-import:B1,27")
      (libsource (lib "eagle-import") (part "TPB1,27"))
    )
    (comp (ref "TP10")
      (value "TPB1,27")
      (footprint "eagle-import:B1,27")
      (libsource (lib "eagle-import") (part "TPB1,27"))
    )
    (comp (ref "TP11")
      (value "TPB1,27")
      (footprint "eagle-import:B1,27")
      (libsource (lib "eagle-import") (part "TPB1,27"))
    )
    (comp (ref "TP12")
      (value "TPB1,27")
      (footprint "eagle-import:B1,27")
      (libsource (lib "eagle-import") (part "TPB1,27"))
    )
    (comp (ref "TP13")
      (value "TPB1,27")
      (footprint "eagle-import:B1,27")
      (libsource (lib "eagle-import") (part "TPB1,27"))
    )
    (comp (ref "TP14")
      (value "TPB1,27")
      (footprint "eagle-import:B1,27")
      (libsource (lib "eagle-import") (part "TPB1,27"))
    )
    (comp (ref "U$1")
      (value "A1162")
      (footprint "eagle-import:A1162-8")
      (libsource (lib "eagle-import") (part "A1162"))
    )
    (comp (ref "U1")
      (value "LTC3558EUDPBF")
      (footprint "eagle-import:QFN-20_UD_LIT")
      (fields (field (name "MANUFACTURER_PART_NUMBER") "ltc3558eud#pbf"))
      (libsource (lib "eagle-import") (part "LTC3558EUDPBF"))
    )
    (comp (ref "U2")
      (value "MAX16054AZT+T")
      (footprint "eagle-import:21-0114C_MXM")
      (fields (field (name "MANUFACTURER_PART_NUMBER") "max16054azt+t"))
      (libsource (lib "eagle-import") (part "MAX16054AZT+T"))
    )
    (comp (ref "U3")
      (value "SPK0641HT4H-1")
      (footprint "eagle-import:SPK0641HT4H-1_KNO")
      (fields (field (name "COPYRIGHT") "Copyright (C) 2018 Accelerated Designs. All rights reserved"))
      (libsource (lib "eagle-import") (part "SPK0641HT4H-1"))
    )
    (comp (ref "U4")
      (value "SPK0641HT4H-1")
      (footprint "eagle-import:SPK0641HT4H-1_KNO")
      (fields (field (name "COPYRIGHT") "Copyright (C) 2018 Accelerated Designs. All rights reserved"))
      (libsource (lib "eagle-import") (part "SPK0641HT4H-1"))
    )
    (comp (ref "U5")
      (value "SPK0641HT4H-1")
      (footprint "eagle-import:SPK0641HT4H-1_KNO")
      (fields (field (name "COPYRIGHT") "Copyright (C) 2018 Accelerated Designs. All rights reserved"))
      (libsource (lib "eagle-import") (part "SPK0641HT4H-1"))
    )
    (comp (ref "U6")
      (value "SPK0641HT4H-1")
      (footprint "eagle-import:SPK0641HT4H-1_KNO")
      (fields (field (name "COPYRIGHT") "Copyright (C) 2018 Accelerated Designs. All rights reserved"))
      (libsource (lib "eagle-import") (part "SPK0641HT4H-1"))
    )
    (comp (ref "U7")
      (value "SPK0641HT4H-1")
      (footprint "eagle-import:SPK0641HT4H-1_KNO")
      (fields (field (name "COPYRIGHT") "Copyright (C) 2018 Accelerated Designs. All rights reserved"))
      (libsource (lib "eagle-import") (part "SPK0641HT4H-1"))
    )
    (comp (ref "U8")
      (value "SPK0641HT4H-1")
      (footprint "eagle-import:SPK0641HT4H-1_KNO")
      (fields (field (name "COPYRIGHT") "Copyright (C) 2018 Accelerated Designs. All rights reserved"))
      (libsource (lib "eagle-import") (part "SPK0641HT4H-1"))
    )
    (comp (ref "UC1")
      (value "2013499-1")
      (footprint "eagle-import:2013499-1")
      (fields (field (name "MOUSER_PART_NUMBER") "571-2013499-1"))
      (libsource (lib "eagle-import") (part "2013499-1"))
    )
    (comp (ref "USB")
      (value "SML-P12MTT86R")
      (footprint "eagle-import:LEDM106X25N")
      (fields (field (name "MOUSER_PART_NUMBER") "755-SML-P12MTT86R"))
      (libsource (lib "eagle-import") (part "SML-P12MTT86R"))
    )
    (comp (ref "XTAL1")
      (value "NX2520SA-16MHZ")
      (footprint "eagle-import:NX2520SA_NDK")
      (fields
        (field (name "MANUFACTURER_PART_NUMBER") "NX2520SA-16MHZ-STD-CSW-4")
        (field (name "COPYRIGHT") "Copyright (C) 2018 Accelerated Designs. All rights reserved")
      )
      (libsource (lib "eagle-import") (part "NX2520SA-16MHZ-STD-CSW-4"))
    )
  )
  (nets
    (net (code "1") (name "/BAT") (class "Default")
      (node (ref "C36") (pin "2") (pinfunction "2_2") (pintype "passive"))
      (node (ref "R49") (pin "1") (pinfunction "1_1") (pintype "passive"))
      (node (ref "U1") (pin "2") (pinfunction "BAT_2") (pintype "output"))
      (node (ref "U1") (pin "7") (pinfunction "PVIN1_7") (pintype "input"))
      (node (ref "U1") (pin "8") (pinfunction "PVIN2_8") (pintype "input"))
    )
    (net (code "2") (name "/BOOT0") (class "Default")
      (node (ref "BOOT") (pin "1") (pinfunction "COM_1") (pintype "passive"))
      (node (ref "BOOT") (pin "2") (pinfunction "COM_2") (pintype "passive"))
      (node (ref "IC1") (pin "61") (pinfunction "PD14_61") (pintype "bidirectional"))
      (node (ref "IC1") (pin "94") (pinfunction "BOOT0_94") (pintype "bidirectional"))
      (node (ref "R61") (pin "2") (pinfunction "2_2") (pintype "passive"))
    )
    (net (code "3") (name "/BOOT1") (class "Default")
      (node (ref "IC1") (pin "37") (pinfunction "PB2_37") (pintype "bidirectional"))
      (node (ref "R63") (pin "2") (pinfunction "2_2") (pintype "passive"))
    )
    (net (code "4") (name "/DAC_OUT1") (class "Default")
      (node (ref "IC1") (pin "29") (pinfunction "PA4_29") (pintype "bidirectional"))
      (node (ref "J12") (pin "2") (pinfunction "2_2") (pintype "passive"))
    )
    (net (code "5") (name "/DAT1") (class "Default")
      (node (ref "J2") (pin "8") (pinfunction "DAT1_8") (pintype "passive"))
      (node (ref "R12") (pin "1") (pinfunction "1_1") (pintype "passive"))
    )
    (net (code "6") (name "/DAT2") (class "Default")
      (node (ref "J2") (pin "1") (pinfunction "DAT2_1") (pintype "passive"))
      (node (ref "R13") (pin "1") (pinfunction "1_1") (pintype "passive"))
    )
    (net (code "7") (name "/DAT3") (class "Default")
      (node (ref "J2") (pin "2") (pinfunction "CD/DAT3^2_2") (pintype "passive"))
      (node (ref "R19") (pin "1") (pinfunction "1_1") (pintype "passive"))
    )
    (net (code "8") (name "/ENCODER_1A") (class "Default")
      (node (ref "J14") (pin "3") (pinfunction "3_3") (pintype "passive"))
      (node (ref "Q1") (pin "3") (pinfunction "D_3") (pintype "passive"))
      (node (ref "R11") (pin "1") (pinfunction "1_1") (pintype "passive"))
      (node (ref "R29") (pin "1") (pinfunction "1_1") (pintype "passive"))
    )
    (net (code "9") (name "/ENCODER_1B") (class "Default")
      (node (ref "J14") (pin "4") (pinfunction "4_4") (pintype "passive"))
      (node (ref "Q2") (pin "3") (pinfunction "D_3") (pintype "passive"))
      (node (ref "R14") (pin "1") (pinfunction "1_1") (pintype "passive"))
      (node (ref "R31") (pin "1") (pinfunction "1_1") (pintype "passive"))
    )
    (net (code "10") (name "/ENCODER_2A") (class "Default")
      (node (ref "J9") (pin "1") (pinfunction "1_1") (pintype "passive"))
      (node (ref "Q3") (pin "3") (pinfunction "D_3") (pintype "passive"))
      (node (ref "R16") (pin "1") (pinfunction "1_1") (pintype "passive"))
      (node (ref "R33") (pin "1") (pinfunction "1_1") (pintype "passive"))
    )
    (net (code "11") (name "/ENCODER_2B") (class "Default")
      (node (ref "J9") (pin "2") (pinfunction "2_2") (pintype "passive"))
      (node (ref "Q4") (pin "3") (pinfunction "D_3") (pintype "passive"))
      (node (ref "R15") (pin "1") (pinfunction "1_1") (pintype "passive"))
      (node (ref "R35") (pin "1") (pinfunction "1_1") (pintype "passive"))
    )
    (net (code "12") (name "/EXTI0_IRQN") (class "Default")
      (node (ref "IC1") (pin "35") (pinfunction "PB0_35") (pintype "bidirectional"))
      (node (ref "Q2") (pin "2") (pinfunction "S_2") (pintype "passive"))
      (node (ref "R30") (pin "1") (pinfunction "1_1") (pintype "passive"))
    )
    (net (code "13") (name "/EXTI1_IRQN") (class "Default")
      (node (ref "IC1") (pin "24") (pinfunction "PA1_24") (pintype "bidirectional"))
      (node (ref "Q3") (pin "2") (pinfunction "S_2") (pintype "passive"))
      (node (ref "R32") (pin "1") (pinfunction "1_1") (pintype "passive"))
    )
    (net (code "14") (name "/EXTI2_IRQN") (class "Default")
      (node (ref "IC1") (pin "25") (pinfunction "PA2_25") (pintype "bidirectional"))
      (node (ref "Q4") (pin "2") (pinfunction "S_2") (pintype "passive"))
      (node (ref "R34") (pin "1") (pinfunction "1_1") (pintype "passive"))
    )
    (net (code "15") (name "/EXTI3_IRQN") (class "Default")
      (node (ref "IC1") (pin "26") (pinfunction "PA3_26") (pintype "bidirectional"))
      (node (ref "Q1") (pin "2") (pinfunction "S_2") (pintype "passive"))
      (node (ref "R28") (pin "1") (pinfunction "1_1") (pintype "passive"))
    )
    (net (code "16") (name "/EXTI8_IRQN") (class "Default")
      (node (ref "IC1") (pin "67") (pinfunction "PA8_67") (pintype "bidirectional"))
      (node (ref "TP10") (pin "TP") (pinfunction "TP_TP") (pintype "input"))
      (node (ref "U$1") (pin "2") (pinfunction "VOUT_2") (pintype "output"))
    )
    (net (code "17") (name "/EXTI11_IRQN") (class "Default")
      (node (ref "IC1") (pin "79") (pinfunction "PC11_79") (pintype "bidirectional"))
      (node (ref "R56") (pin "1") (pinfunction "1_1") (pintype "passive"))
      (node (ref "SW1") (pin "3") (pinfunction "NO_3") (pintype "passive"))
      (node (ref "SW1") (pin "4") (pinfunction "NO_4") (pintype "passive"))
    )
    (net (code "18") (name "/EXTI14_IRQN") (class "Default")
      (node (ref "IC1") (pin "53") (pinfunction "PB14_53") (pintype "bidirectional"))
      (node (ref "J2") (pin "10") (pinfunction "DETECT_SWITCH_10") (pintype "passive"))
    )
    (net (code "19") (name "/EXTI15_IRQN") (class "Default")
      (node (ref "IC1") (pin "77") (pinfunction "PA15_77") (pintype "bidirectional"))
      (node (ref "R57") (pin "1") (pinfunction "1_1") (pintype "passive"))
      (node (ref "SW2") (pin "3") (pinfunction "NO_3") (pintype "passive"))
      (node (ref "SW2") (pin "4") (pinfunction "NO_4") (pintype "passive"))
    )
    (net (code "20") (name "/FMPI2C1_SCL") (class "Default")
      (node (ref "J1") (pin "4") (pinfunction "4_4") (pintype "passive"))
      (node (ref "J5") (pin "4") (pinfunction "4_4") (pintype "passive"))
      (node (ref "R51") (pin "1") (pinfunction "1_1") (pintype "passive"))
      (node (ref "R59") (pin "1") (pinfunction "1_1") (pintype "passive"))
    )
    (net (code "21") (name "/FMPI2C1_SDA") (class "Default")
      (node (ref "J1") (pin "3") (pinfunction "3_3") (pintype "passive"))
      (node (ref "J5") (pin "3") (pinfunction "3_3") (pintype "passive"))
      (node (ref "R4") (pin "1") (pinfunction "1_1") (pintype "passive"))
      (node (ref "R42") (pin "1") (pinfunction "1_1") (pintype "passive"))
    )
    (net (code "22") (name "/GPIO_PA10") (class "Default")
      (node (ref "IC1") (pin "69") (pinfunction "PA10_69") (pintype "bidirectional"))
      (node (ref "J3") (pin "2") (pinfunction "2_2") (pintype "passive"))
    )
    (net (code "23") (name "/GPIO_PB9") (class "Default")
      (node (ref "IC1") (pin "96") (pinfunction "PB9_96") (pintype "bidirectional"))
      (node (ref "J6") (pin "2") (pinfunction "2_2") (pintype "passive"))
    )
    (net (code "24") (name "/I2C1_SCL") (class "Default")
      (node (ref "P100") (pin "10") (pinfunction "10_10") (pintype "passive"))
      (node (ref "R53") (pin "2") (pinfunction "2_2") (pintype "passive"))
    )
    (net (code "25") (name "/I2C1_SDA") (class "Default")
      (node (ref "P100") (pin "9") (pinfunction "9_9") (pintype "passive"))
      (node (ref "R64") (pin "2") (pinfunction "2_2") (pintype "passive"))
    )
    (net (code "26") (name "/I2S1_CK") (class "Default")
      (node (ref "IC1") (pin "4") (pinfunction "PE5_4") (pintype "bidirectional"))
      (node (ref "IC1") (pin "89") (pinfunction "PB3_89") (pintype "bidirectional"))
      (node (ref "R55") (pin "2") (pinfunction "2_2") (pintype "passive"))
      (node (ref "R9") (pin "1") (pinfunction "1_1") (pintype "passive"))
      (node (ref "R9") (pin "2") (pinfunction "2_2") (pintype "passive"))
      (node (ref "TP5") (pin "TP") (pinfunction "TP_TP") (pintype "input"))
      (node (ref "U3") (pin "2") (pinfunction "CLOCK_2") (pintype "input"))
    )
    (net (code "27") (name "/I2S1_SD") (class "Default")
      (node (ref "IC1") (pin "32") (pinfunction "PA7_32") (pintype "bidirectional"))
      (node (ref "R26") (pin "2") (pinfunction "2_2") (pintype "passive"))
      (node (ref "TP7") (pin "TP") (pinfunction "TP_TP") (pintype "input"))
    )
    (net (code "28") (name "/I2S2_SD") (class "Default")
      (node (ref "IC1") (pin "54") (pinfunction "PB15_54") (pintype "bidirectional"))
      (node (ref "R10") (pin "2") (pinfunction "2_2") (pintype "passive"))
      (node (ref "TP8") (pin "TP") (pinfunction "TP_TP") (pintype "input"))
    )
    (net (code "29") (name "/I2S3_SD") (class "Default")
      (node (ref "IC1") (pin "81") (pinfunction "PD0_81") (pintype "bidirectional"))
      (node (ref "R27") (pin "2") (pinfunction "2_2") (pintype "passive"))
      (node (ref "TP9") (pin "TP") (pinfunction "TP_TP") (pintype "input"))
    )
    (net (code "30") (name "/I2SX_CK") (class "Default")
      (node (ref "R54") (pin "2") (pinfunction "2_2") (pintype "passive"))
      (node (ref "U4") (pin "2") (pinfunction "CLOCK_2") (pintype "input"))
      (node (ref "U5") (pin "2") (pinfunction "CLOCK_2") (pintype "input"))
      (node (ref "U6") (pin "2") (pinfunction "CLOCK_2") (pintype "input"))
      (node (ref "U7") (pin "2") (pinfunction "CLOCK_2") (pintype "input"))
      (node (ref "U8") (pin "2") (pinfunction "CLOCK_2") (pintype "input"))
    )
    (net (code "31") (name "/IMU_PSEL0") (class "Default")
      (node (ref "P100") (pin "2") (pinfunction "2_2") (pintype "passive"))
      (node (ref "PSEL2") (pin "2") (pinfunction "2_2") (pintype "passive"))
    )
    (net (code "32") (name "/IMU_PSEL1") (class "Default")
      (node (ref "P100") (pin "1") (pinfunction "1_1") (pintype "passive"))
      (node (ref "PSEL1") (pin "2") (pinfunction "2_2") (pintype "passive"))
    )
    (net (code "33") (name "/IMU_RESET") (class "Default")
      (node (ref "IC1") (pin "85") (pinfunction "PD4_85") (pintype "bidirectional"))
      (node (ref "P102") (pin "5") (pinfunction "5_5") (pintype "passive"))
    )
    (net (code "34") (name "/IMU_SYNC_IN") (class "Default")
      (node (ref "IC1") (pin "88") (pinfunction "PD7_88") (pintype "bidirectional"))
      (node (ref "P102") (pin "8") (pinfunction "8_8") (pintype "passive"))
    )
    (net (code "35") (name "/IMU_SYNC_OUT") (class "Default")
      (node (ref "IC1") (pin "87") (pinfunction "PD6_87") (pintype "bidirectional"))
      (node (ref "P102") (pin "7") (pinfunction "7_7") (pintype "passive"))
    )
    (net (code "36") (name "/IMU_SYNC_PPS") (class "Default")
      (node (ref "IC1") (pin "86") (pinfunction "PD5_86") (pintype "bidirectional"))
      (node (ref "P102") (pin "6") (pinfunction "6_6") (pintype "passive"))
    )
    (net (code "37") (name "/IO_LED1") (class "Default")
      (node (ref "IC1") (pin "41") (pinfunction "PE10_41") (pintype "bidirectional"))
      (node (ref "R5") (pin "2") (pinfunction "2_2") (pintype "passive"))
    )
    (net (code "38") (name "/IO_LED2") (class "Default")
      (node (ref "IC1") (pin "40") (pinfunction "PE9_40") (pintype "bidirectional"))
      (node (ref "R7") (pin "2") (pinfunction "2_2") (pintype "passive"))
    )
    (net (code "39") (name "/IO_LED3") (class "Default")
      (node (ref "IC1") (pin "39") (pinfunction "PE8_39") (pintype "bidirectional"))
      (node (ref "R22") (pin "2") (pinfunction "2_2") (pintype "passive"))
    )
    (net (code "40") (name "/IO_LED4") (class "Default")
      (node (ref "IC1") (pin "38") (pinfunction "PE7_38") (pintype "bidirectional"))
      (node (ref "R23") (pin "2") (pinfunction "2_2") (pintype "passive"))
    )
    (net (code "41") (name "/IO_LED5") (class "Default")
      (node (ref "IC1") (pin "36") (pinfunction "PB1_36") (pintype "bidirectional"))
      (node (ref "R18") (pin "2") (pinfunction "2_2") (pintype "passive"))
    )
    (net (code "42") (name "/IO_LED6") (class "Default")
      (node (ref "IC1") (pin "34") (pinfunction "PC5_34") (pintype "bidirectional"))
      (node (ref "R21") (pin "2") (pinfunction "2_2") (pintype "passive"))
    )
    (net (code "43") (name "/IO_MAG_DIAG") (class "Default")
      (node (ref "IC1") (pin "66") (pinfunction "PC9_66") (pintype "bidirectional"))
      (node (ref "U$1") (pin "6") (pinfunction "DIAG_6") (pintype "bidirectional"))
    )
    (net (code "44") (name "/IO_MOTOR_DIR") (class "Default")
      (node (ref "IC1") (pin "33") (pinfunction "PC4_33") (pintype "bidirectional"))
      (node (ref "J12") (pin "3") (pinfunction "3_3") (pintype "passive"))
    )
    (net (code "45") (name "/IO_MUX_MIC") (class "Default")
      (node (ref "IC1") (pin "52") (pinfunction "PB13_52") (pintype "bidirectional"))
      (node (ref "MUX1") (pin "2") (pinfunction "1IN_2") (pintype "input"))
    )
    (net (code "46") (name "/MODE") (class "Default")
      (node (ref "JP4") (pin "2") (pinfunction "2_2") (pintype "passive"))
      (node (ref "R17") (pin "2") (pinfunction "2_2") (pintype "passive"))
      (node (ref "U1") (pin "3") (pinfunction "MODE_3") (pintype "passive"))
    )
    (net (code "47") (name "/MOTOR+") (class "Default")
      (node (ref "J10") (pin "1") (pinfunction "1_1") (pintype "passive"))
      (node (ref "J14") (pin "6") (pinfunction "6_6") (pintype "passive"))
    )
    (net (code "48") (name "/MOTOR-") (class "Default")
      (node (ref "J10") (pin "2") (pinfunction "2_2") (pintype "passive"))
      (node (ref "J14") (pin "5") (pinfunction "5_5") (pintype "passive"))
    )
    (net (code "49") (name "/OSC_IN") (class "Default")
      (node (ref "C22") (pin "2") (pinfunction "2_2") (pintype "passive"))
      (node (ref "IC1") (pin "12") (pinfunction "PH0-OSC_IN_12") (pintype "bidirectional"))
      (node (ref "XTAL1") (pin "1") (pinfunction "1_1") (pintype "passive"))
    )
    (net (code "50") (name "/OSC_OUT") (class "Default")
      (node (ref "IC1") (pin "13") (pinfunction "PH1-OSC_OUT_13") (pintype "bidirectional"))
      (node (ref "R67") (pin "2") (pinfunction "2_2") (pintype "passive"))
    )
    (net (code "51") (name "/OTG_FS_DM") (class "Default")
      (node (ref "CP1") (pin "3") (pinfunction "D-IN_3") (pintype "bidirectional"))
      (node (ref "IC1") (pin "70") (pinfunction "PA11_70") (pintype "bidirectional"))
    )
    (net (code "52") (name "/OTG_FS_DP") (class "Default")
      (node (ref "CP1") (pin "1") (pinfunction "D+IN_1") (pintype "bidirectional"))
      (node (ref "IC1") (pin "71") (pinfunction "PA12_71") (pintype "bidirectional"))
    )
    (net (code "53") (name "/OUT") (class "Default")
      (node (ref "C15") (pin "1") (pinfunction "+_1") (pintype "bidirectional"))
      (node (ref "C33") (pin "1") (pinfunction "1_1") (pintype "passive"))
      (node (ref "CR1") (pin "8") (pinfunction "OUT_8") (pintype "power_in"))
      (node (ref "R48") (pin "1") (pinfunction "1_1") (pintype "passive"))
    )
    (net (code "54") (name "/PMIC_CHRG") (class "Default")
      (node (ref "CHRG") (pin "1") (pinfunction "K_1") (pintype "bidirectional"))
      (node (ref "U1") (pin "19") (pinfunction "~{CHRG}_19") (pintype "output"))
    )
    (net (code "55") (name "/PMIC_EN2") (class "Default")
      (node (ref "R41") (pin "2") (pinfunction "2_2") (pintype "passive"))
      (node (ref "R50") (pin "2") (pinfunction "2_2") (pintype "passive"))
      (node (ref "TP6") (pin "TP") (pinfunction "TP_TP") (pintype "input"))
      (node (ref "U1") (pin "15") (pinfunction "EN2_15") (pintype "input"))
    )
    (net (code "56") (name "/RESET") (class "Default")
      (node (ref "C20") (pin "2") (pinfunction "2_2") (pintype "passive"))
      (node (ref "IC1") (pin "14") (pinfunction "NRST_14") (pintype "bidirectional"))
      (node (ref "J7") (pin "1") (pinfunction "1_1") (pintype "passive"))
      (node (ref "RESET") (pin "1") (pinfunction "COM_1") (pintype "passive"))
      (node (ref "RESET") (pin "2") (pinfunction "COM_2") (pintype "passive"))
      (node (ref "TP14") (pin "TP") (pinfunction "TP_TP") (pintype "input"))
    )
    (net (code "57") (name "/SDIO_CK") (class "Default")
      (node (ref "J2") (pin "5") (pinfunction "CLK_5") (pintype "passive"))
      (node (ref "R52") (pin "2") (pinfunction "2_2") (pintype "passive"))
    )
    (net (code "58") (name "/SDIO_CMD") (class "Default")
      (node (ref "J2") (pin "3") (pinfunction "CMD_3") (pintype "passive"))
      (node (ref "R20") (pin "1") (pinfunction "1_1") (pintype "passive"))
      (node (ref "R65") (pin "2") (pinfunction "2_2") (pintype "passive"))
    )
    (net (code "59") (name "/SDIO_D0") (class "Default")
      (node (ref "J2") (pin "7") (pinfunction "DAT0_7") (pintype "passive"))
      (node (ref "R1") (pin "1") (pinfunction "1_1") (pintype "passive"))
      (node (ref "R60") (pin "1") (pinfunction "1_1") (pintype "passive"))
    )
    (net (code "60") (name "/SPI4_CS1") (class "Default")
      (node (ref "IC1") (pin "42") (pinfunction "PE11_42") (pintype "bidirectional"))
      (node (ref "P2") (pin "3") (pinfunction "3_3") (pintype "passive"))
    )
    (net (code "61") (name "/SPI4_CS2") (class "Default")
      (node (ref "IC1") (pin "51") (pinfunction "PB12_51") (pintype "bidirectional"))
      (node (ref "P3") (pin "3") (pinfunction "3_3") (pintype "passive"))
    )
    (net (code "62") (name "/SPI4_MISO") (class "Default")
      (node (ref "IC1") (pin "44") (pinfunction "PE13_44") (pintype "bidirectional"))
      (node (ref "P2") (pin "5") (pinfunction "5_5") (pintype "passive"))
      (node (ref "P3") (pin "5") (pinfunction "5_5") (pintype "passive"))
      (node (ref "R3") (pin "2") (pinfunction "2_2") (pintype "passive"))
    )
    (net (code "63") (name "/SPI4_MOSI") (class "Default")
      (node (ref "P100") (pin "4") (pinfunction "4_4") (pintype "passive"))
      (node (ref "P2") (pin "4") (pinfunction "4_4") (pintype "passive"))
      (node (ref "P3") (pin "4") (pinfunction "4_4") (pintype "passive"))
      (node (ref "R62") (pin "1") (pinfunction "1_1") (pintype "passive"))
    )
    (net (code "64") (name "/SPI4_SCK") (class "Default")
      (node (ref "P100") (pin "6") (pinfunction "6_6") (pintype "passive"))
      (node (ref "P2") (pin "6") (pinfunction "6_6") (pintype "passive"))
      (node (ref "P3") (pin "6") (pinfunction "6_6") (pintype "passive"))
      (node (ref "R38") (pin "1") (pinfunction "1_1") (pintype "passive"))
    )
    (net (code "65") (name "/SPI_CS_IMU") (class "Default")
      (node (ref "IC1") (pin "90") (pinfunction "PB4_90") (pintype "bidirectional"))
      (node (ref "P100") (pin "3") (pinfunction "3_3") (pintype "passive"))
    )
    (net (code "66") (name "/SWCLK") (class "Default")
      (node (ref "IC1") (pin "76") (pinfunction "PA14_76") (pintype "bidirectional"))
      (node (ref "J7") (pin "3") (pinfunction "3_3") (pintype "passive"))
    )
    (net (code "67") (name "/SWDIO") (class "Default")
      (node (ref "IC1") (pin "72") (pinfunction "PA13_72") (pintype "bidirectional"))
      (node (ref "J7") (pin "4") (pinfunction "4_4") (pintype "passive"))
    )
    (net (code "68") (name "/TIM9_CH2") (class "Default")
      (node (ref "IC1") (pin "30") (pinfunction "PA5_30") (pintype "bidirectional"))
      (node (ref "IC1") (pin "47") (pinfunction "PB10_47") (pintype "bidirectional"))
      (node (ref "IC1") (pin "5") (pinfunction "PE6_5") (pintype "bidirectional"))
      (node (ref "IC1") (pin "78") (pinfunction "PC10_78") (pintype "bidirectional"))
    )
    (net (code "69") (name "/USART3_CLK") (class "Default")
      (node (ref "J8") (pin "1") (pinfunction "1_1") (pintype "passive"))
      (node (ref "R40") (pin "1") (pinfunction "1_1") (pintype "passive"))
    )
    (net (code "70") (name "/USART3_CTS") (class "Default")
      (node (ref "IC1") (pin "58") (pinfunction "PD11_58") (pintype "bidirectional"))
      (node (ref "J8") (pin "2") (pinfunction "2_2") (pintype "passive"))
      (node (ref "P102") (pin "4") (pinfunction "4_4") (pintype "passive"))
    )
    (net (code "71") (name "/USART3_RTS") (class "Default")
      (node (ref "IC1") (pin "59") (pinfunction "PD12_59") (pintype "bidirectional"))
      (node (ref "J8") (pin "3") (pinfunction "3_3") (pintype "passive"))
      (node (ref "P102") (pin "3") (pinfunction "3_3") (pintype "passive"))
    )
    (net (code "72") (name "/USART3_RX") (class "Default")
      (node (ref "J8") (pin "5") (pinfunction "5_5") (pintype "passive"))
      (node (ref "P102") (pin "1") (pinfunction "1_1") (pintype "passive"))
      (node (ref "R6") (pin "1") (pinfunction "1_1") (pintype "passive"))
    )
    (net (code "73") (name "/USART3_TX") (class "Default")
      (node (ref "J8") (pin "4") (pinfunction "4_4") (pintype "passive"))
      (node (ref "P102") (pin "2") (pinfunction "2_2") (pintype "passive"))
      (node (ref "R58") (pin "1") (pinfunction "1_1") (pintype "passive"))
    )
    (net (code "74") (name "/VOUT2") (class "Default")
      (node (ref "C41") (pin "2") (pinfunction "2_2") (pintype "passive"))
      (node (ref "R43") (pin "2") (pinfunction "2_2") (pintype "passive"))
      (node (ref "R45") (pin "2") (pinfunction "2_2") (pintype "passive"))
      (node (ref "R47") (pin "1") (pinfunction "1_1") (pintype "passive"))
      (node (ref "U1") (pin "11") (pinfunction "VOUT2_11") (pintype "power_in"))
    )
    (net (code "75") (name "GND") (class "Default")
      (node (ref "C1") (pin "1") (pinfunction "1_1") (pintype "passive"))
      (node (ref "C14") (pin "2") (pinfunction "2_2") (pintype "passive"))
      (node (ref "C15") (pin "2") (pinfunction "-_2") (pintype "bidirectional"))
      (node (ref "C16") (pin "1") (pinfunction "1_1") (pintype "passive"))
      (node (ref "C17") (pin "1") (pinfunction "1_1") (pintype "passive"))
      (node (ref "C18") (pin "1") (pinfunction "1_1") (pintype "passive"))
      (node (ref "C19") (pin "1") (pinfunction "1_1") (pintype "passive"))
      (node (ref "C2") (pin "1") (pinfunction "1_1") (pintype "passive"))
      (node (ref "C20") (pin "1") (pinfunction "1_1") (pintype "passive"))
      (node (ref "C22") (pin "1") (pinfunction "1_1") (pintype "passive"))
      (node (ref "C23") (pin "1") (pinfunction "1_1") (pintype "passive"))
      (node (ref "C24") (pin "1") (pinfunction "1_1") (pintype "passive"))
      (node (ref "C25") (pin "1") (pinfunction "1_1") (pintype "passive"))
      (node (ref "C26") (pin "1") (pinfunction "1_1") (pintype "passive"))
      (node (ref "C27") (pin "1") (pinfunction "1_1") (pintype "passive"))
      (node (ref "C28") (pin "1") (pinfunction "1_1") (pintype "passive"))
      (node (ref "C29") (pin "1") (pinfunction "1_1") (pintype "passive"))
      (node (ref "C3") (pin "1") (pinfunction "1_1") (pintype "passive"))
      (node (ref "C30") (pin "1") (pinfunction "1_1") (pintype "passive"))
      (node (ref "C31") (pin "1") (pinfunction "1_1") (pintype "passive"))
      (node (ref "C32") (pin "2") (pinfunction "-_2") (pintype "bidirectional"))
      (node (ref "C33") (pin "2") (pinfunction "2_2") (pintype "passive"))
      (node (ref "C34") (pin "1") (pinfunction "1_1") (pintype "passive"))
      (node (ref "C36") (pin "1") (pinfunction "1_1") (pintype "passive"))
      (node (ref "C4") (pin "1") (pinfunction "1_1") (pintype "passive"))
      (node (ref "C41") (pin "1") (pinfunction "1_1") (pintype "passive"))
      (node (ref "C5") (pin "1") (pinfunction "1_1") (pintype "passive"))
      (node (ref "C6") (pin "1") (pinfunction "1_1") (pintype "passive"))
      (node (ref "C7") (pin "1") (pinfunction "1_1") (pintype "passive"))
      (node (ref "C8") (pin "1") (pinfunction "1_1") (pintype "passive"))
      (node (ref "CP1") (pin "2") (pinfunction "GND_2") (pintype "power_in"))
      (node (ref "CR1") (pin "1") (pinfunction "FB_1") (pintype "power_in"))
      (node (ref "CR1") (pin "6") (pinfunction "GND_6") (pintype "passive"))
      (node (ref "IC1") (pin "10") (pinfunction "VSS_1_10") (pintype "power_in"))
      (node (ref "IC1") (pin "20") (pinfunction "VSSA/VREF-_20") (pintype "power_in"))
      (node (ref "IC1") (pin "27") (pinfunction "VSS_2_27") (pintype "power_in"))
      (node (ref "IC1") (pin "49") (pinfunction "VSS_3_49") (pintype "power_in"))
      (node (ref "IC1") (pin "74") (pinfunction "VSS_4_74") (pintype "power_in"))
      (node (ref "IC1") (pin "99") (pinfunction "VSS_5_99") (pintype "power_in"))
      (node (ref "J1") (pin "1") (pinfunction "1_1") (pintype "passive"))
      (node (ref "J12") (pin "1") (pinfunction "1_1") (pintype "passive"))
      (node (ref "J14") (pin "2") (pinfunction "2_2") (pintype "passive"))
      (node (ref "J2") (pin "6") (pinfunction "VSS_6") (pintype "power_in"))
      (node (ref "J2") (pin "9") (pinfunction "VSS_9") (pintype "power_in"))
      (node (ref "J2") (pin "P1") (pinfunction "SHIELD_P1") (pintype "passive"))
      (node (ref "J2") (pin "P2") (pinfunction "SHIELD_P2") (pintype "passive"))
      (node (ref "J2") (pin "P3") (pinfunction "SHIELD_P3") (pintype "passive"))
      (node (ref "J2") (pin "P4") (pinfunction "SHIELD_P4") (pintype "passive"))
      (node (ref "J3") (pin "1") (pinfunction "1_1") (pintype "passive"))
      (node (ref "J4") (pin "1") (pinfunction "1_1") (pintype "passive"))
      (node (ref "J5") (pin "1") (pinfunction "1_1") (pintype "passive"))
      (node (ref "J6") (pin "1") (pinfunction "1_1") (pintype "passive"))
      (node (ref "J7") (pin "2") (pinfunction "2_2") (pintype "passive"))
      (node (ref "J9") (pin "4") (pinfunction "4_4") (pintype "passive"))
      (node (ref "J9") (pin "5") (pinfunction "5_5") (pintype "passive"))
      (node (ref "JP1") (pin "1") (pinfunction "1_1") (pintype "passive"))
      (node (ref "JP4") (pin "1") (pinfunction "1_1") (pintype "passive"))
      (node (ref "JST_BAT") (pin "1") (pinfunction "1_1") (pintype "passive"))
      (node (ref "LED1") (pin "1") (pinfunction "K_1") (pintype "bidirectional"))
      (node (ref "LED2") (pin "1") (pinfunction "K_1") (pintype "bidirectional"))
      (node (ref "LED3") (pin "1") (pinfunction "K_1") (pintype "bidirectional"))
      (node (ref "LED4") (pin "1") (pinfunction "K_1") (pintype "bidirectional"))
      (node (ref "LED5") (pin "1") (pinfunction "K_1") (pintype "bidirectional"))
      (node (ref "LED6") (pin "1") (pinfunction "K_1") (pintype "bidirectional"))
      (node (ref "MUX1") (pin "5") (pinfunction "1S2_5") (pintype "bidirectional"))
      (node (ref "MUX1") (pin "6") (pinfunction "GND_6") (pintype "passive"))
      (node (ref "MUX1") (pin "7") (pinfunction "2IN_7") (pintype "input"))
      (node (ref "P100") (pin "7") (pinfunction "7_7") (pintype "passive"))
      (node (ref "P101") (pin "2") (pinfunction "2_2") (pintype "passive"))
      (node (ref "P101") (pin "3") (pinfunction "3_3") (pintype "passive"))
      (node (ref "P2") (pin "1") (pinfunction "1_1") (pintype "passive"))
      (node (ref "P3") (pin "1") (pinfunction "1_1") (pintype "passive"))
      (node (ref "POWER") (pin "1") (pinfunction "COM_1") (pintype "passive"))
      (node (ref "POWER") (pin "2") (pinfunction "COM_2") (pintype "passive"))
      (node (ref "PSEL1") (pin "1") (pinfunction "1_1") (pintype "passive"))
      (node (ref "PSEL2") (pin "1") (pinfunction "1_1") (pintype "passive"))
      (node (ref "PWR") (pin "1") (pinfunction "K_1") (pintype "bidirectional"))
      (node (ref "R17") (pin "1") (pinfunction "1_1") (pintype "passive"))
      (node (ref "R37") (pin "2") (pinfunction "2_2") (pintype "passive"))
      (node (ref "R41") (pin "1") (pinfunction "1_1") (pintype "passive"))
      (node (ref "R44") (pin "1") (pinfunction "1_1") (pintype "passive"))
      (node (ref "R61") (pin "1") (pinfunction "1_1") (pintype "passive"))
      (node (ref "R63") (pin "1") (pinfunction "1_1") (pintype "passive"))
      (node (ref "RESET") (pin "3") (pinfunction "NO_3") (pintype "passive"))
      (node (ref "RESET") (pin "4") (pinfunction "NO_4") (pintype "passive"))
      (node (ref "SW1") (pin "1") (pinfunction "COM_1") (pintype "passive"))
      (node (ref "SW1") (pin "2") (pinfunction "COM_2") (pintype "passive"))
      (node (ref "SW2") (pin "1") (pinfunction "COM_1") (pintype "passive"))
      (node (ref "SW2") (pin "2") (pinfunction "COM_2") (pintype "passive"))
      (node (ref "U$1") (pin "1") (pinfunction "NC/GND_1") (pintype "power_in"))
      (node (ref "U$1") (pin "3") (pinfunction "GND_3") (pintype "power_in"))
      (node (ref "U$1") (pin "4") (pinfunction "GND_4") (pintype "power_in"))
      (node (ref "U$1") (pin "7") (pinfunction "NC/GND_7") (pintype "power_in"))
      (node (ref "U$1") (pin "8") (pinfunction "NC/GND_8") (pintype "power_in"))
      (node (ref "U1") (pin "1") (pinfunction "GND_1") (pintype "power_in"))
      (node (ref "U1") (pin "12") (pinfunction "SUSP_12") (pintype "passive"))
      (node (ref "U1") (pin "17") (pinfunction "NTC_17") (pintype "input"))
      (node (ref "U1") (pin "21") (pinfunction "21_21") (pintype "passive"))
      (node (ref "U1") (pin "5") (pinfunction "EN1_5") (pintype "input"))
      (node (ref "U1") (pin "P$1") (pinfunction "21_P$1") (pintype "passive"))
      (node (ref "U1") (pin "P$2") (pinfunction "21_P$2") (pintype "passive"))
      (node (ref "U1") (pin "P$3") (pinfunction "21_P$3") (pintype "passive"))
      (node (ref "U1") (pin "P$4") (pinfunction "21_P$4") (pintype "passive"))
      (node (ref "U2") (pin "2") (pinfunction "GND_2") (pintype "power_in"))
      (node (ref "U2") (pin "3") (pinfunction "CLEAR_3") (pintype "input"))
      (node (ref "U3") (pin "5") (pinfunction "GROUND_2_5") (pintype "passive"))
      (node (ref "U3") (pin "6") (pinfunction "GROUND_3_6") (pintype "passive"))
      (node (ref "U3") (pin "7") (pinfunction "GROUND_4_7") (pintype "passive"))
      (node (ref "U3") (pin "8") (pinfunction "GROUND_8") (pintype "passive"))
      (node (ref "U4") (pin "3") (pinfunction "SELECT_3") (pintype "input"))
      (node (ref "U4") (pin "5") (pinfunction "GROUND_2_5") (pintype "passive"))
      (node (ref "U4") (pin "6") (pinfunction "GROUND_3_6") (pintype "passive"))
      (node (ref "U4") (pin "7") (pinfunction "GROUND_4_7") (pintype "passive"))
      (node (ref "U4") (pin "8") (pinfunction "GROUND_8") (pintype "passive"))
      (node (ref "U5") (pin "5") (pinfunction "GROUND_2_5") (pintype "passive"))
      (node (ref "U5") (pin "6") (pinfunction "GROUND_3_6") (pintype "passive"))
      (node (ref "U5") (pin "7") (pinfunction "GROUND_4_7") (pintype "passive"))
      (node (ref "U5") (pin "8") (pinfunction "GROUND_8") (pintype "passive"))
      (node (ref "U6") (pin "3") (pinfunction "SELECT_3") (pintype "input"))
      (node (ref "U6") (pin "5") (pinfunction "GROUND_2_5") (pintype "passive"))
      (node (ref "U6") (pin "6") (pinfunction "GROUND_3_6") (pintype "passive"))
      (node (ref "U6") (pin "7") (pinfunction "GROUND_4_7") (pintype "passive"))
      (node (ref "U6") (pin "8") (pinfunction "GROUND_8") (pintype "passive"))
      (node (ref "U7") (pin "5") (pinfunction "GROUND_2_5") (pintype "passive"))
      (node (ref "U7") (pin "6") (pinfunction "GROUND_3_6") (pintype "passive"))
      (node (ref "U7") (pin "7") (pinfunction "GROUND_4_7") (pintype "passive"))
      (node (ref "U7") (pin "8") (pinfunction "GROUND_8") (pintype "passive"))
      (node (ref "U8") (pin "3") (pinfunction "SELECT_3") (pintype "input"))
      (node (ref "U8") (pin "5") (pinfunction "GROUND_2_5") (pintype "passive"))
      (node (ref "U8") (pin "6") (pinfunction "GROUND_3_6") (pintype "passive"))
      (node (ref "U8") (pin "7") (pinfunction "GROUND_4_7") (pintype "passive"))
      (node (ref "U8") (pin "8") (pinfunction "GROUND_8") (pintype "passive"))
      (node (ref "UC1") (pin "5") (pinfunction "5_5") (pintype "power_in"))
      (node (ref "UC1") (pin "6") (pinfunction "5_6") (pintype "power_in"))
      (node (ref "UC1") (pin "7") (pinfunction "5_7") (pintype "power_in"))
      (node (ref "UC1") (pin "8") (pinfunction "5_8") (pintype "power_in"))
      (node (ref "UC1") (pin "9") (pinfunction "5_9") (pintype "power_in"))
      (node (ref "USB") (pin "1") (pinfunction "K_1") (pintype "bidirectional"))
      (node (ref "XTAL1") (pin "2") (pinfunction "2_2") (pintype "passive"))
      (node (ref "XTAL1") (pin "4") (pinfunction "4_4") (pintype "passive"))
    )
    (net (code "76") (name "Net-(C31-Pad2)") (class "Default")
      (node (ref "C31") (pin "2") (pinfunction "2_2") (pintype "passive"))
      (node (ref "R67") (pin "1") (pinfunction "1_1") (pintype "passive"))
      (node (ref "XTAL1") (pin "3") (pinfunction "3_3") (pintype "passive"))
    )
    (net (code "77") (name "Net-(C38-Pad2)") (class "Default")
      (node (ref "C38") (pin "2") (pinfunction "2_2") (pintype "passive"))
      (node (ref "R45") (pin "1") (pinfunction "1_1") (pintype "passive"))
    )
    (net (code "78") (name "Net-(C39-Pad2)") (class "Default")
      (node (ref "C39") (pin "2") (pinfunction "2_2") (pintype "passive"))
      (node (ref "R46") (pin "1") (pinfunction "1_1") (pintype "passive"))
    )
    (net (code "79") (name "Net-(CHRG-A)") (class "Default")
      (node (ref "CHRG") (pin "2") (pinfunction "A_2") (pintype "bidirectional"))
      (node (ref "R39") (pin "1") (pinfunction "1_1") (pintype "passive"))
    )
    (net (code "80") (name "Net-(CP1-D+OUT)") (class "Default")
      (node (ref "CP1") (pin "6") (pinfunction "D+OUT_6") (pintype "bidirectional"))
      (node (ref "UC1") (pin "3") (pinfunction "3_3") (pintype "bidirectional"))
    )
    (net (code "81") (name "Net-(CP1-D-OUT)") (class "Default")
      (node (ref "CP1") (pin "4") (pinfunction "D-OUT_4") (pintype "bidirectional"))
      (node (ref "UC1") (pin "2") (pinfunction "2_2") (pintype "bidirectional"))
    )
    (net (code "82") (name "Net-(CR1-LX)") (class "Default")
      (node (ref "CR1") (pin "7") (pinfunction "LX_7") (pintype "passive"))
      (node (ref "L1") (pin "2") (pinfunction "2_2") (pintype "bidirectional"))
    )
    (net (code "83") (name "Net-(CR1-REF)") (class "Default")
      (node (ref "C34") (pin "2") (pinfunction "2_2") (pintype "passive"))
      (node (ref "CR1") (pin "4") (pinfunction "REF_4") (pintype "power_in"))
    )
    (net (code "84") (name "Net-(CR1-~{SHDN})") (class "Default")
      (node (ref "CR1") (pin "5") (pinfunction "~{SHDN}_5") (pintype "passive"))
      (node (ref "JP1") (pin "2") (pinfunction "2_2") (pintype "passive"))
    )
    (net (code "85") (name "Net-(IC1-PB6)") (class "Default")
      (node (ref "IC1") (pin "92") (pinfunction "PB6_92") (pintype "bidirectional"))
      (node (ref "R53") (pin "1") (pinfunction "1_1") (pintype "passive"))
    )
    (net (code "86") (name "Net-(IC1-PB7)") (class "Default")
      (node (ref "IC1") (pin "93") (pinfunction "PB7_93") (pintype "bidirectional"))
      (node (ref "R64") (pin "1") (pinfunction "1_1") (pintype "passive"))
    )
    (net (code "87") (name "Net-(IC1-PC6)") (class "Default")
      (node (ref "IC1") (pin "63") (pinfunction "PC6_63") (pintype "bidirectional"))
      (node (ref "R51") (pin "2") (pinfunction "2_2") (pintype "passive"))
    )
    (net (code "88") (name "Net-(IC1-PC7)") (class "Default")
      (node (ref "IC1") (pin "64") (pinfunction "PC7_64") (pintype "bidirectional"))
      (node (ref "R4") (pin "2") (pinfunction "2_2") (pintype "passive"))
    )
    (net (code "89") (name "Net-(IC1-PC8)") (class "Default")
      (node (ref "IC1") (pin "65") (pinfunction "PC8_65") (pintype "bidirectional"))
      (node (ref "R60") (pin "2") (pinfunction "2_2") (pintype "passive"))
      (node (ref "TP12") (pin "TP") (pinfunction "TP_TP") (pintype "input"))
    )
    (net (code "90") (name "Net-(IC1-PC12)") (class "Default")
      (node (ref "IC1") (pin "80") (pinfunction "PC12_80") (pintype "bidirectional"))
      (node (ref "R52") (pin "1") (pinfunction "1_1") (pintype "passive"))
      (node (ref "TP13") (pin "TP") (pinfunction "TP_TP") (pintype "input"))
    )
    (net (code "91") (name "Net-(IC1-PD2)") (class "Default")
      (node (ref "IC1") (pin "83") (pinfunction "PD2_83") (pintype "bidirectional"))
      (node (ref "R65") (pin "1") (pinfunction "1_1") (pintype "passive"))
      (node (ref "TP11") (pin "TP") (pinfunction "TP_TP") (pintype "input"))
    )
    (net (code "92") (name "Net-(IC1-PD8)") (class "Default")
      (node (ref "IC1") (pin "55") (pinfunction "PD8_55") (pintype "bidirectional"))
      (node (ref "R58") (pin "2") (pinfunction "2_2") (pintype "passive"))
    )
    (net (code "93") (name "Net-(IC1-PD9)") (class "Default")
      (node (ref "IC1") (pin "56") (pinfunction "PD9_56") (pintype "bidirectional"))
      (node (ref "R6") (pin "2") (pinfunction "2_2") (pintype "passive"))
    )
    (net (code "94") (name "Net-(IC1-PD10)") (class "Default")
      (node (ref "IC1") (pin "57") (pinfunction "PD10_57") (pintype "bidirectional"))
      (node (ref "R40") (pin "2") (pinfunction "2_2") (pintype "passive"))
    )
    (net (code "95") (name "Net-(IC1-PE12)") (class "Default")
      (node (ref "IC1") (pin "43") (pinfunction "PE12_43") (pintype "bidirectional"))
      (node (ref "R38") (pin "2") (pinfunction "2_2") (pintype "passive"))
    )
    (net (code "96") (name "Net-(IC1-PE14)") (class "Default")
      (node (ref "IC1") (pin "45") (pinfunction "PE14_45") (pintype "bidirectional"))
      (node (ref "R62") (pin "2") (pinfunction "2_2") (pintype "passive"))
    )
    (net (code "97") (name "Net-(IC1-VCAP_1)") (class "Default")
      (node (ref "C17") (pin "2") (pinfunction "2_2") (pintype "passive"))
      (node (ref "IC1") (pin "48") (pinfunction "VCAP_1_48") (pintype "power_in"))
    )
    (net (code "98") (name "Net-(IC1-VCAP_2)") (class "Default")
      (node (ref "C16") (pin "2") (pinfunction "2_2") (pintype "passive"))
      (node (ref "IC1") (pin "73") (pinfunction "VCAP_2_73") (pintype "power_in"))
    )
    (net (code "99") (name "Net-(LED1-A)") (class "Default")
      (node (ref "LED1") (pin "2") (pinfunction "A_2") (pintype "bidirectional"))
      (node (ref "R5") (pin "1") (pinfunction "1_1") (pintype "passive"))
    )
    (net (code "100") (name "Net-(LED2-A)") (class "Default")
      (node (ref "LED2") (pin "2") (pinfunction "A_2") (pintype "bidirectional"))
      (node (ref "R7") (pin "1") (pinfunction "1_1") (pintype "passive"))
    )
    (net (code "101") (name "Net-(LED3-A)") (class "Default")
      (node (ref "LED3") (pin "2") (pinfunction "A_2") (pintype "bidirectional"))
      (node (ref "R22") (pin "1") (pinfunction "1_1") (pintype "passive"))
    )
    (net (code "102") (name "Net-(LED4-A)") (class "Default")
      (node (ref "LED4") (pin "2") (pinfunction "A_2") (pintype "bidirectional"))
      (node (ref "R23") (pin "1") (pinfunction "1_1") (pintype "passive"))
    )
    (net (code "103") (name "Net-(LED5-A)") (class "Default")
      (node (ref "LED5") (pin "2") (pinfunction "A_2") (pintype "bidirectional"))
      (node (ref "R18") (pin "1") (pinfunction "1_1") (pintype "passive"))
    )
    (net (code "104") (name "Net-(LED6-A)") (class "Default")
      (node (ref "LED6") (pin "2") (pinfunction "A_2") (pintype "bidirectional"))
      (node (ref "R21") (pin "1") (pinfunction "1_1") (pintype "passive"))
    )
    (net (code "105") (name "Net-(MUX1-1S1)") (class "Default")
      (node (ref "MUX1") (pin "3") (pinfunction "1S1_3") (pintype "bidirectional"))
      (node (ref "R55") (pin "1") (pinfunction "1_1") (pintype "passive"))
    )
    (net (code "106") (name "Net-(MUX1-D1)") (class "Default")
      (node (ref "MUX1") (pin "4") (pinfunction "D1_4") (pintype "bidirectional"))
      (node (ref "R54") (pin "1") (pinfunction "1_1") (pintype "passive"))
    )
    (net (code "107") (name "Net-(P100-Pad5)") (class "Default")
      (node (ref "P100") (pin "5") (pinfunction "5_5") (pintype "passive"))
      (node (ref "R3") (pin "1") (pinfunction "1_1") (pintype "passive"))
    )
    (net (code "108") (name "Net-(PSEL1-Pad3)") (class "Default")
      (node (ref "PSEL1") (pin "3") (pinfunction "3_3") (pintype "passive"))
      (node (ref "R2") (pin "1") (pinfunction "1_1") (pintype "passive"))
    )
    (net (code "109") (name "Net-(PSEL2-Pad3)") (class "Default")
      (node (ref "PSEL2") (pin "3") (pinfunction "3_3") (pintype "passive"))
      (node (ref "R8") (pin "1") (pinfunction "1_1") (pintype "passive"))
    )
    (net (code "110") (name "Net-(PWR-A)") (class "Default")
      (node (ref "PWR") (pin "2") (pinfunction "A_2") (pintype "bidirectional"))
      (node (ref "R24") (pin "1") (pinfunction "1_1") (pintype "passive"))
    )
    (net (code "111") (name "Net-(R36-Pad2)") (class "Default")
      (node (ref "R36") (pin "2") (pinfunction "2_2") (pintype "passive"))
      (node (ref "R37") (pin "1") (pinfunction "1_1") (pintype "passive"))
    )
    (net (code "112") (name "Net-(U1-FB2)") (class "Default")
      (node (ref "C38") (pin "1") (pinfunction "1_1") (pintype "passive"))
      (node (ref "C40") (pin "2") (pinfunction "2_2") (pintype "passive"))
      (node (ref "R43") (pin "1") (pinfunction "1_1") (pintype "passive"))
      (node (ref "R44") (pin "2") (pinfunction "2_2") (pintype "passive"))
      (node (ref "R46") (pin "2") (pinfunction "2_2") (pintype "passive"))
      (node (ref "U1") (pin "13") (pinfunction "FB2_13") (pintype "passive"))
    )
    (net (code "113") (name "Net-(U1-PROG)") (class "Default")
      (node (ref "R36") (pin "1") (pinfunction "1_1") (pintype "passive"))
      (node (ref "U1") (pin "18") (pinfunction "PROG_18") (pintype "passive"))
    )
    (net (code "114") (name "Net-(U1-SWAB2)") (class "Default")
      (node (ref "L3") (pin "2") (pinfunction "2_2") (pintype "bidirectional"))
      (node (ref "U1") (pin "9") (pinfunction "SWAB2_9") (pintype "passive"))
    )
    (net (code "115") (name "Net-(U1-SWCD2)") (class "Default")
      (node (ref "L3") (pin "1") (pinfunction "1_1") (pintype "bidirectional"))
      (node (ref "U1") (pin "10") (pinfunction "SWCD2_10") (pintype "passive"))
    )
    (net (code "116") (name "Net-(U1-VC2)") (class "Default")
      (node (ref "C39") (pin "1") (pinfunction "1_1") (pintype "passive"))
      (node (ref "C40") (pin "1") (pinfunction "1_1") (pintype "passive"))
      (node (ref "U1") (pin "14") (pinfunction "VC2_14") (pintype "output"))
    )
    (net (code "117") (name "Net-(U2-IN)") (class "Default")
      (node (ref "POWER") (pin "3") (pinfunction "NO_3") (pintype "passive"))
      (node (ref "POWER") (pin "4") (pinfunction "NO_4") (pintype "passive"))
      (node (ref "U2") (pin "1") (pinfunction "IN_1") (pintype "input"))
    )
    (net (code "118") (name "Net-(U2-OUT)") (class "Default")
      (node (ref "R50") (pin "1") (pinfunction "1_1") (pintype "passive"))
      (node (ref "U2") (pin "5") (pinfunction "OUT_5") (pintype "output"))
    )
    (net (code "119") (name "Net-(U3-DATA)") (class "Default")
      (node (ref "R26") (pin "1") (pinfunction "1_1") (pintype "passive"))
      (node (ref "U3") (pin "1") (pinfunction "DATA_1") (pintype "output"))
      (node (ref "U4") (pin "1") (pinfunction "DATA_1") (pintype "output"))
    )
    (net (code "120") (name "Net-(U5-DATA)") (class "Default")
      (node (ref "R10") (pin "1") (pinfunction "1_1") (pintype "passive"))
      (node (ref "U5") (pin "1") (pinfunction "DATA_1") (pintype "output"))
      (node (ref "U6") (pin "1") (pinfunction "DATA_1") (pintype "output"))
    )
    (net (code "121") (name "Net-(U7-DATA)") (class "Default")
      (node (ref "R27") (pin "1") (pinfunction "1_1") (pintype "passive"))
      (node (ref "U7") (pin "1") (pinfunction "DATA_1") (pintype "output"))
      (node (ref "U8") (pin "1") (pinfunction "DATA_1") (pintype "output"))
    )
    (net (code "122") (name "Net-(USB-A)") (class "Default")
      (node (ref "R25") (pin "1") (pinfunction "1_1") (pintype "passive"))
      (node (ref "USB") (pin "2") (pinfunction "A_2") (pintype "bidirectional"))
    )
    (net (code "123") (name "VCC_1") (class "Default")
      (node (ref "BOOT") (pin "3") (pinfunction "NO_3") (pintype "passive"))
      (node (ref "BOOT") (pin "4") (pinfunction "NO_4") (pintype "passive"))
      (node (ref "C14") (pin "1") (pinfunction "1_1") (pintype "passive"))
      (node (ref "C18") (pin "2") (pinfunction "2_2") (pintype "passive"))
      (node (ref "C19") (pin "2") (pinfunction "2_2") (pintype "passive"))
      (node (ref "C23") (pin "2") (pinfunction "2_2") (pintype "passive"))
      (node (ref "C24") (pin "2") (pinfunction "2_2") (pintype "passive"))
      (node (ref "C25") (pin "2") (pinfunction "2_2") (pintype "passive"))
      (node (ref "C26") (pin "2") (pinfunction "2_2") (pintype "passive"))
      (node (ref "C27") (pin "2") (pinfunction "2_2") (pintype "passive"))
      (node (ref "C28") (pin "2") (pinfunction "2_2") (pintype "passive"))
      (node (ref "C29") (pin "2") (pinfunction "2_2") (pintype "passive"))
      (node (ref "C3") (pin "2") (pinfunction "2_2") (pintype "passive"))
      (node (ref "C30") (pin "2") (pinfunction "2_2") (pintype "passive"))
      (node (ref "C32") (pin "1") (pinfunction "+_1") (pintype "bidirectional"))
      (node (ref "C4") (pin "2") (pinfunction "2_2") (pintype "passive"))
      (node (ref "C5") (pin "2") (pinfunction "2_2") (pintype "passive"))
      (node (ref "C6") (pin "2") (pinfunction "2_2") (pintype "passive"))
      (node (ref "C7") (pin "2") (pinfunction "2_2") (pintype "passive"))
      (node (ref "C8") (pin "2") (pinfunction "2_2") (pintype "passive"))
      (node (ref "IC1") (pin "100") (pinfunction "VDD_6_100") (pintype "power_in"))
      (node (ref "IC1") (pin "11") (pinfunction "VDD_1_11") (pintype "power_in"))
      (node (ref "IC1") (pin "19") (pinfunction "VDD_2_19") (pintype "power_in"))
      (node (ref "IC1") (pin "21") (pinfunction "VREF+_21") (pintype "power_in"))
      (node (ref "IC1") (pin "22") (pinfunction "VDDA_22") (pintype "power_in"))
      (node (ref "IC1") (pin "28") (pinfunction "VDD_3_28") (pintype "power_in"))
      (node (ref "IC1") (pin "50") (pinfunction "VDD_4_50") (pintype "power_in"))
      (node (ref "IC1") (pin "6") (pinfunction "VBAT_6") (pintype "power_in"))
      (node (ref "IC1") (pin "75") (pinfunction "VDD_5_75") (pintype "power_in"))
      (node (ref "J1") (pin "2") (pinfunction "2_2") (pintype "passive"))
      (node (ref "J2") (pin "4") (pinfunction "VDD_4") (pintype "power_in"))
      (node (ref "J4") (pin "2") (pinfunction "2_2") (pintype "passive"))
      (node (ref "J5") (pin "2") (pinfunction "2_2") (pintype "passive"))
      (node (ref "JP1") (pin "3") (pinfunction "3_3") (pintype "passive"))
      (node (ref "L1") (pin "1") (pinfunction "1_1") (pintype "bidirectional"))
      (node (ref "MUX1") (pin "1") (pinfunction "VCC_1") (pintype "power_in"))
      (node (ref "P101") (pin "5") (pinfunction "5_5") (pintype "passive"))
      (node (ref "P2") (pin "2") (pinfunction "2_2") (pintype "passive"))
      (node (ref "P3") (pin "2") (pinfunction "2_2") (pintype "passive"))
      (node (ref "Q1") (pin "1") (pinfunction "G_1") (pintype "passive"))
      (node (ref "Q2") (pin "1") (pinfunction "G_1") (pintype "passive"))
      (node (ref "Q3") (pin "1") (pinfunction "G_1") (pintype "passive"))
      (node (ref "Q4") (pin "1") (pinfunction "G_1") (pintype "passive"))
      (node (ref "R1") (pin "2") (pinfunction "2_2") (pintype "passive"))
      (node (ref "R12") (pin "2") (pinfunction "2_2") (pintype "passive"))
      (node (ref "R13") (pin "2") (pinfunction "2_2") (pintype "passive"))
      (node (ref "R19") (pin "2") (pinfunction "2_2") (pintype "passive"))
      (node (ref "R2") (pin "2") (pinfunction "2_2") (pintype "passive"))
      (node (ref "R20") (pin "2") (pinfunction "2_2") (pintype "passive"))
      (node (ref "R24") (pin "2") (pinfunction "2_2") (pintype "passive"))
      (node (ref "R28") (pin "2") (pinfunction "2_2") (pintype "passive"))
      (node (ref "R30") (pin "2") (pinfunction "2_2") (pintype "passive"))
      (node (ref "R32") (pin "2") (pinfunction "2_2") (pintype "passive"))
      (node (ref "R34") (pin "2") (pinfunction "2_2") (pintype "passive"))
      (node (ref "R42") (pin "2") (pinfunction "2_2") (pintype "passive"))
      (node (ref "R47") (pin "2") (pinfunction "2_2") (pintype "passive"))
      (node (ref "R56") (pin "2") (pinfunction "2_2") (pintype "passive"))
      (node (ref "R57") (pin "2") (pinfunction "2_2") (pintype "passive"))
      (node (ref "R59") (pin "2") (pinfunction "2_2") (pintype "passive"))
      (node (ref "R8") (pin "2") (pinfunction "2_2") (pintype "passive"))
      (node (ref "TP2") (pin "TP") (pinfunction "TP_TP") (pintype "input"))
      (node (ref "U$1") (pin "5") (pinfunction "VCC_5") (pintype "power_in"))
      (node (ref "U3") (pin "3") (pinfunction "SELECT_3") (pintype "input"))
      (node (ref "U3") (pin "4") (pinfunction "VDD_4") (pintype "power_in"))
      (node (ref "U4") (pin "4") (pinfunction "VDD_4") (pintype "power_in"))
      (node (ref "U5") (pin "3") (pinfunction "SELECT_3") (pintype "input"))
      (node (ref "U5") (pin "4") (pinfunction "VDD_4") (pintype "power_in"))
      (node (ref "U6") (pin "4") (pinfunction "VDD_4") (pintype "power_in"))
      (node (ref "U7") (pin "3") (pinfunction "SELECT_3") (pintype "input"))
      (node (ref "U7") (pin "4") (pinfunction "VDD_4") (pintype "power_in"))
      (node (ref "U8") (pin "4") (pinfunction "VDD_4") (pintype "power_in"))
    )
    (net (code "124") (name "VCC_2") (class "Default")
      (node (ref "JP4") (pin "3") (pinfunction "3_3") (pintype "passive"))
      (node (ref "JST_BAT") (pin "2") (pinfunction "2_2") (pintype "passive"))
      (node (ref "R49") (pin "2") (pinfunction "2_2") (pintype "passive"))
      (node (ref "TP3") (pin "TP") (pinfunction "TP_TP") (pintype "input"))
      (node (ref "U2") (pin "6") (pinfunction "VCC_6") (pintype "power_in"))
    )
    (net (code "125") (name "VOUT") (class "Default")
      (node (ref "J14") (pin "1") (pinfunction "1_1") (pintype "passive"))
      (node (ref "J9") (pin "3") (pinfunction "3_3") (pintype "passive"))
      (node (ref "R11") (pin "2") (pinfunction "2_2") (pintype "passive"))
      (node (ref "R14") (pin "2") (pinfunction "2_2") (pintype "passive"))
      (node (ref "R15") (pin "2") (pinfunction "2_2") (pintype "passive"))
      (node (ref "R16") (pin "2") (pinfunction "2_2") (pintype "passive"))
      (node (ref "R29") (pin "2") (pinfunction "2_2") (pintype "passive"))
      (node (ref "R31") (pin "2") (pinfunction "2_2") (pintype "passive"))
      (node (ref "R33") (pin "2") (pinfunction "2_2") (pintype "passive"))
      (node (ref "R35") (pin "2") (pinfunction "2_2") (pintype "passive"))
      (node (ref "R48") (pin "2") (pinfunction "2_2") (pintype "passive"))
      (node (ref "TP4") (pin "TP") (pinfunction "TP_TP") (pintype "input"))
    )
    (net (code "126") (name "V_USB") (class "Default")
      (node (ref "C1") (pin "2") (pinfunction "2_2") (pintype "passive"))
      (node (ref "C2") (pin "2") (pinfunction "2_2") (pintype "passive"))
      (node (ref "CP1") (pin "5") (pinfunction "VBUS_5") (pintype "bidirectional"))
      (node (ref "R25") (pin "2") (pinfunction "2_2") (pintype "passive"))
      (node (ref "R39") (pin "2") (pinfunction "2_2") (pintype "passive"))
      (node (ref "TP1") (pin "TP") (pinfunction "TP_TP") (pintype "input"))
      (node (ref "U1") (pin "16") (pinfunction "HPWR_16") (pintype "passive"))
      (node (ref "U1") (pin "20") (pinfunction "VCC_20") (pintype "power_in"))
      (node (ref "UC1") (pin "1") (pinfunction "1_1") (pintype "power_in"))
    )
    (net (code "127") (name "unconnected-(CR1-LBI-Pad2)") (class "Default")
      (node (ref "CR1") (pin "2") (pinfunction "LBI_2") (pintype "bidirectional"))
    )
    (net (code "128") (name "unconnected-(CR1-~{LBO}-Pad3)") (class "Default")
      (node (ref "CR1") (pin "3") (pinfunction "~{LBO}_3") (pintype "output"))
    )
    (net (code "129") (name "unconnected-(IC1-PA0-Pad23)") (class "Default")
      (node (ref "IC1") (pin "23") (pinfunction "PA0_23") (pintype "bidirectional"))
    )
    (net (code "130") (name "unconnected-(IC1-PA6-Pad31)") (class "Default")
      (node (ref "IC1") (pin "31") (pinfunction "PA6_31") (pintype "bidirectional"))
    )
    (net (code "131") (name "unconnected-(IC1-PA9-Pad68)") (class "Default")
      (node (ref "IC1") (pin "68") (pinfunction "PA9_68") (pintype "no_connect"))
    )
    (net (code "132") (name "unconnected-(IC1-PB-Pad95)") (class "Default")
      (node (ref "IC1") (pin "95") (pinfunction "PB_95") (pintype "bidirectional"))
    )
    (net (code "133") (name "unconnected-(IC1-PB5-Pad91)") (class "Default")
      (node (ref "IC1") (pin "91") (pinfunction "PB5_91") (pintype "bidirectional"))
    )
    (net (code "134") (name "unconnected-(IC1-PC0-Pad15)") (class "Default")
      (node (ref "IC1") (pin "15") (pinfunction "PC0_15") (pintype "bidirectional"))
    )
    (net (code "135") (name "unconnected-(IC1-PC1-Pad16)") (class "Default")
      (node (ref "IC1") (pin "16") (pinfunction "PC1_16") (pintype "bidirectional"))
    )
    (net (code "136") (name "unconnected-(IC1-PC2-Pad17)") (class "Default")
      (node (ref "IC1") (pin "17") (pinfunction "PC2_17") (pintype "bidirectional"))
    )
    (net (code "137") (name "unconnected-(IC1-PC3-Pad18)") (class "Default")
      (node (ref "IC1") (pin "18") (pinfunction "PC3_18") (pintype "bidirectional"))
    )
    (net (code "138") (name "unconnected-(IC1-PC13-Pad7)") (class "Default")
      (node (ref "IC1") (pin "7") (pinfunction "PC13_7") (pintype "bidirectional"))
    )
    (net (code "139") (name "unconnected-(IC1-PC14-OSC32_IN-Pad8)") (class "Default")
      (node (ref "IC1") (pin "8") (pinfunction "PC14-OSC32_IN_8") (pintype "bidirectional"))
    )
    (net (code "140") (name "unconnected-(IC1-PC15-OSC32_OUT-Pad9)") (class "Default")
      (node (ref "IC1") (pin "9") (pinfunction "PC15-OSC32_OUT_9") (pintype "bidirectional"))
    )
    (net (code "141") (name "unconnected-(IC1-PD1-Pad82)") (class "Default")
      (node (ref "IC1") (pin "82") (pinfunction "PD1_82") (pintype "bidirectional"))
    )
    (net (code "142") (name "unconnected-(IC1-PD3-Pad84)") (class "Default")
      (node (ref "IC1") (pin "84") (pinfunction "PD3_84") (pintype "bidirectional"))
    )
    (net (code "143") (name "unconnected-(IC1-PD13-Pad60)") (class "Default")
      (node (ref "IC1") (pin "60") (pinfunction "PD13_60") (pintype "bidirectional"))
    )
    (net (code "144") (name "unconnected-(IC1-PD15-Pad62)") (class "Default")
      (node (ref "IC1") (pin "62") (pinfunction "PD15_62") (pintype "bidirectional"))
    )
    (net (code "145") (name "unconnected-(IC1-PE0-Pad97)") (class "Default")
      (node (ref "IC1") (pin "97") (pinfunction "PE0_97") (pintype "bidirectional"))
    )
    (net (code "146") (name "unconnected-(IC1-PE1-Pad98)") (class "Default")
      (node (ref "IC1") (pin "98") (pinfunction "PE1_98") (pintype "bidirectional"))
    )
    (net (code "147") (name "unconnected-(IC1-PE2-Pad1)") (class "Default")
      (node (ref "IC1") (pin "1") (pinfunction "PE2_1") (pintype "bidirectional"))
    )
    (net (code "148") (name "unconnected-(IC1-PE3-Pad2)") (class "Default")
      (node (ref "IC1") (pin "2") (pinfunction "PE3_2") (pintype "bidirectional"))
    )
    (net (code "149") (name "unconnected-(IC1-PE4-Pad3)") (class "Default")
      (node (ref "IC1") (pin "3") (pinfunction "PE4_3") (pintype "bidirectional"))
    )
    (net (code "150") (name "unconnected-(IC1-PE15-Pad46)") (class "Default")
      (node (ref "IC1") (pin "46") (pinfunction "PE15_46") (pintype "bidirectional"))
    )
    (net (code "151") (name "unconnected-(MUX1-2S1-Pad8)") (class "Default")
      (node (ref "MUX1") (pin "8") (pinfunction "2S1_8") (pintype "bidirectional"))
    )
    (net (code "152") (name "unconnected-(MUX1-2S2-Pad10)") (class "Default")
      (node (ref "MUX1") (pin "10") (pinfunction "2S2_10") (pintype "bidirectional"))
    )
    (net (code "153") (name "unconnected-(MUX1-D2-Pad9)") (class "Default")
      (node (ref "MUX1") (pin "9") (pinfunction "D2_9") (pintype "bidirectional"))
    )
    (net (code "154") (name "unconnected-(P100-Pad8)") (class "Default")
      (node (ref "P100") (pin "8") (pinfunction "8_8") (pintype "passive"))
    )
    (net (code "155") (name "unconnected-(P101-Pad1)") (class "Default")
      (node (ref "P101") (pin "1") (pinfunction "1_1") (pintype "passive"))
    )
    (net (code "156") (name "unconnected-(P101-Pad4)") (class "Default")
      (node (ref "P101") (pin "4") (pinfunction "4_4") (pintype "passive"))
    )
    (net (code "157") (name "unconnected-(P101-Pad6)") (class "Default")
      (node (ref "P101") (pin "6") (pinfunction "6_6") (pintype "passive"))
    )
    (net (code "158") (name "unconnected-(P101-Pad7)") (class "Default")
      (node (ref "P101") (pin "7") (pinfunction "7_7") (pintype "passive"))
    )
    (net (code "159") (name "unconnected-(P101-Pad8)") (class "Default")
      (node (ref "P101") (pin "8") (pinfunction "8_8") (pintype "passive"))
    )
    (net (code "160") (name "unconnected-(P103-Pad1)") (class "Default")
      (node (ref "P103") (pin "1") (pinfunction "1_1") (pintype "passive"))
    )
    (net (code "161") (name "unconnected-(P103-Pad2)") (class "Default")
      (node (ref "P103") (pin "2") (pinfunction "2_2") (pintype "passive"))
    )
    (net (code "162") (name "unconnected-(P103-Pad3)") (class "Default")
      (node (ref "P103") (pin "3") (pinfunction "3_3") (pintype "passive"))
    )
    (net (code "163") (name "unconnected-(P103-Pad4)") (class "Default")
      (node (ref "P103") (pin "4") (pinfunction "4_4") (pintype "passive"))
    )
    (net (code "164") (name "unconnected-(P103-Pad5)") (class "Default")
      (node (ref "P103") (pin "5") (pinfunction "5_5") (pintype "passive"))
    )
    (net (code "165") (name "unconnected-(P103-Pad6)") (class "Default")
      (node (ref "P103") (pin "6") (pinfunction "6_6") (pintype "passive"))
    )
    (net (code "166") (name "unconnected-(U1-FB1-Pad4)") (class "Default")
      (node (ref "U1") (pin "4") (pinfunction "FB1_4") (pintype "passive"))
    )
    (net (code "167") (name "unconnected-(U1-SW1-Pad6)") (class "Default")
      (node (ref "U1") (pin "6") (pinfunction "SW1_6") (pintype "passive"))
    )
    (net (code "168") (name "unconnected-(U2-~{OUT}-Pad4)") (class "Default")
      (node (ref "U2") (pin "4") (pinfunction "~{OUT}_4") (pintype "output"))
    )
    (net (code "169") (name "unconnected-(UC1-Pad4)") (class "Default")
      (node (ref "UC1") (pin "4") (pinfunction "4_4") (pintype "no_connect"))
    )
  )
)
